# Titan_v1p5.net
KiCad netlist of a schematic drawn in EAGLE
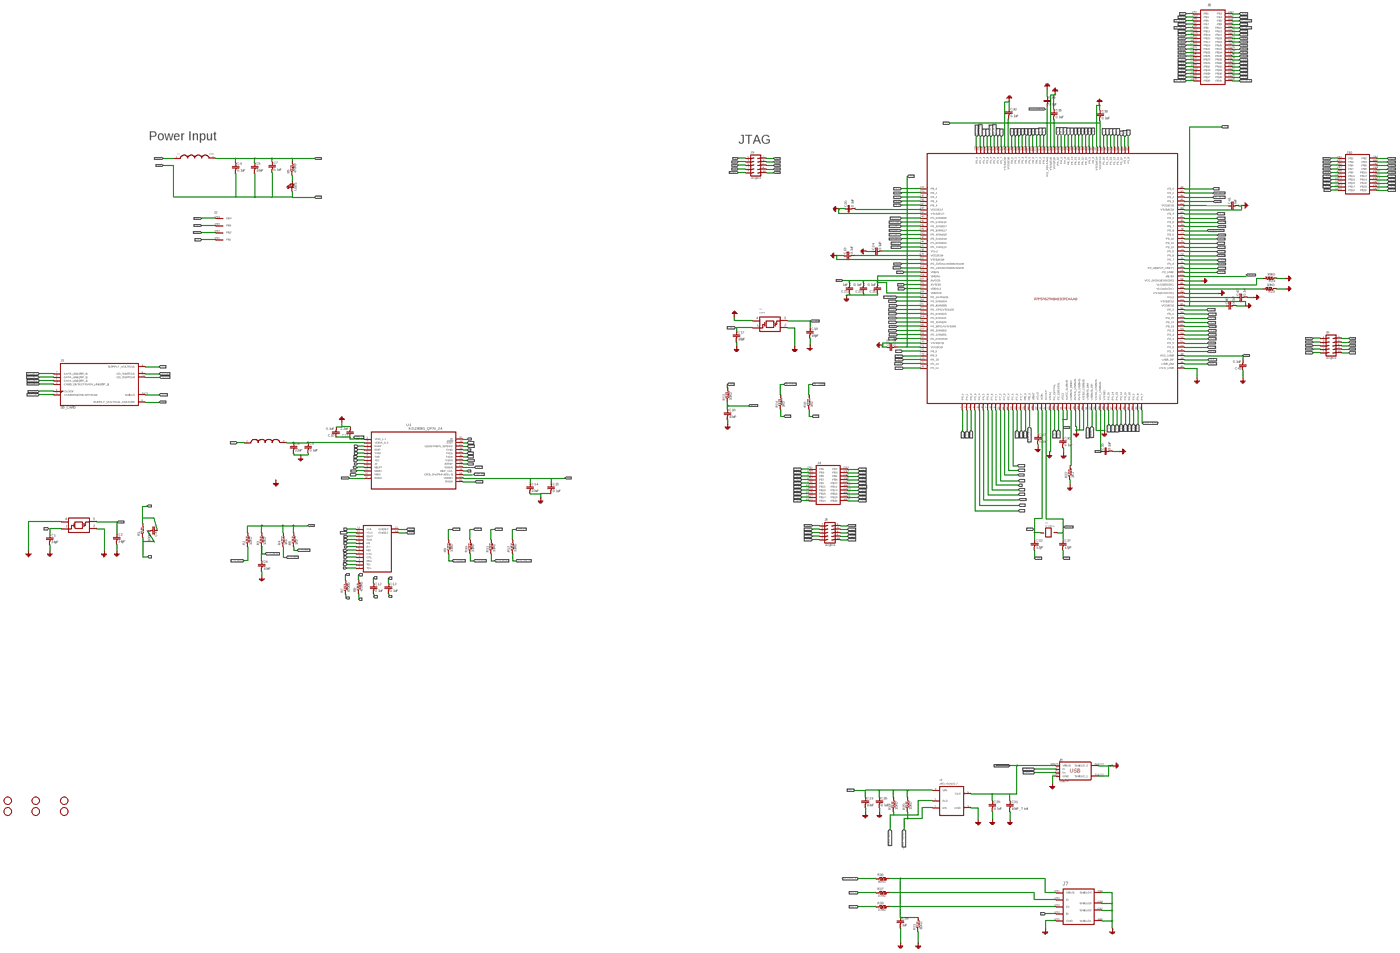
[diagram p0: schematic, sheet 1, overview]
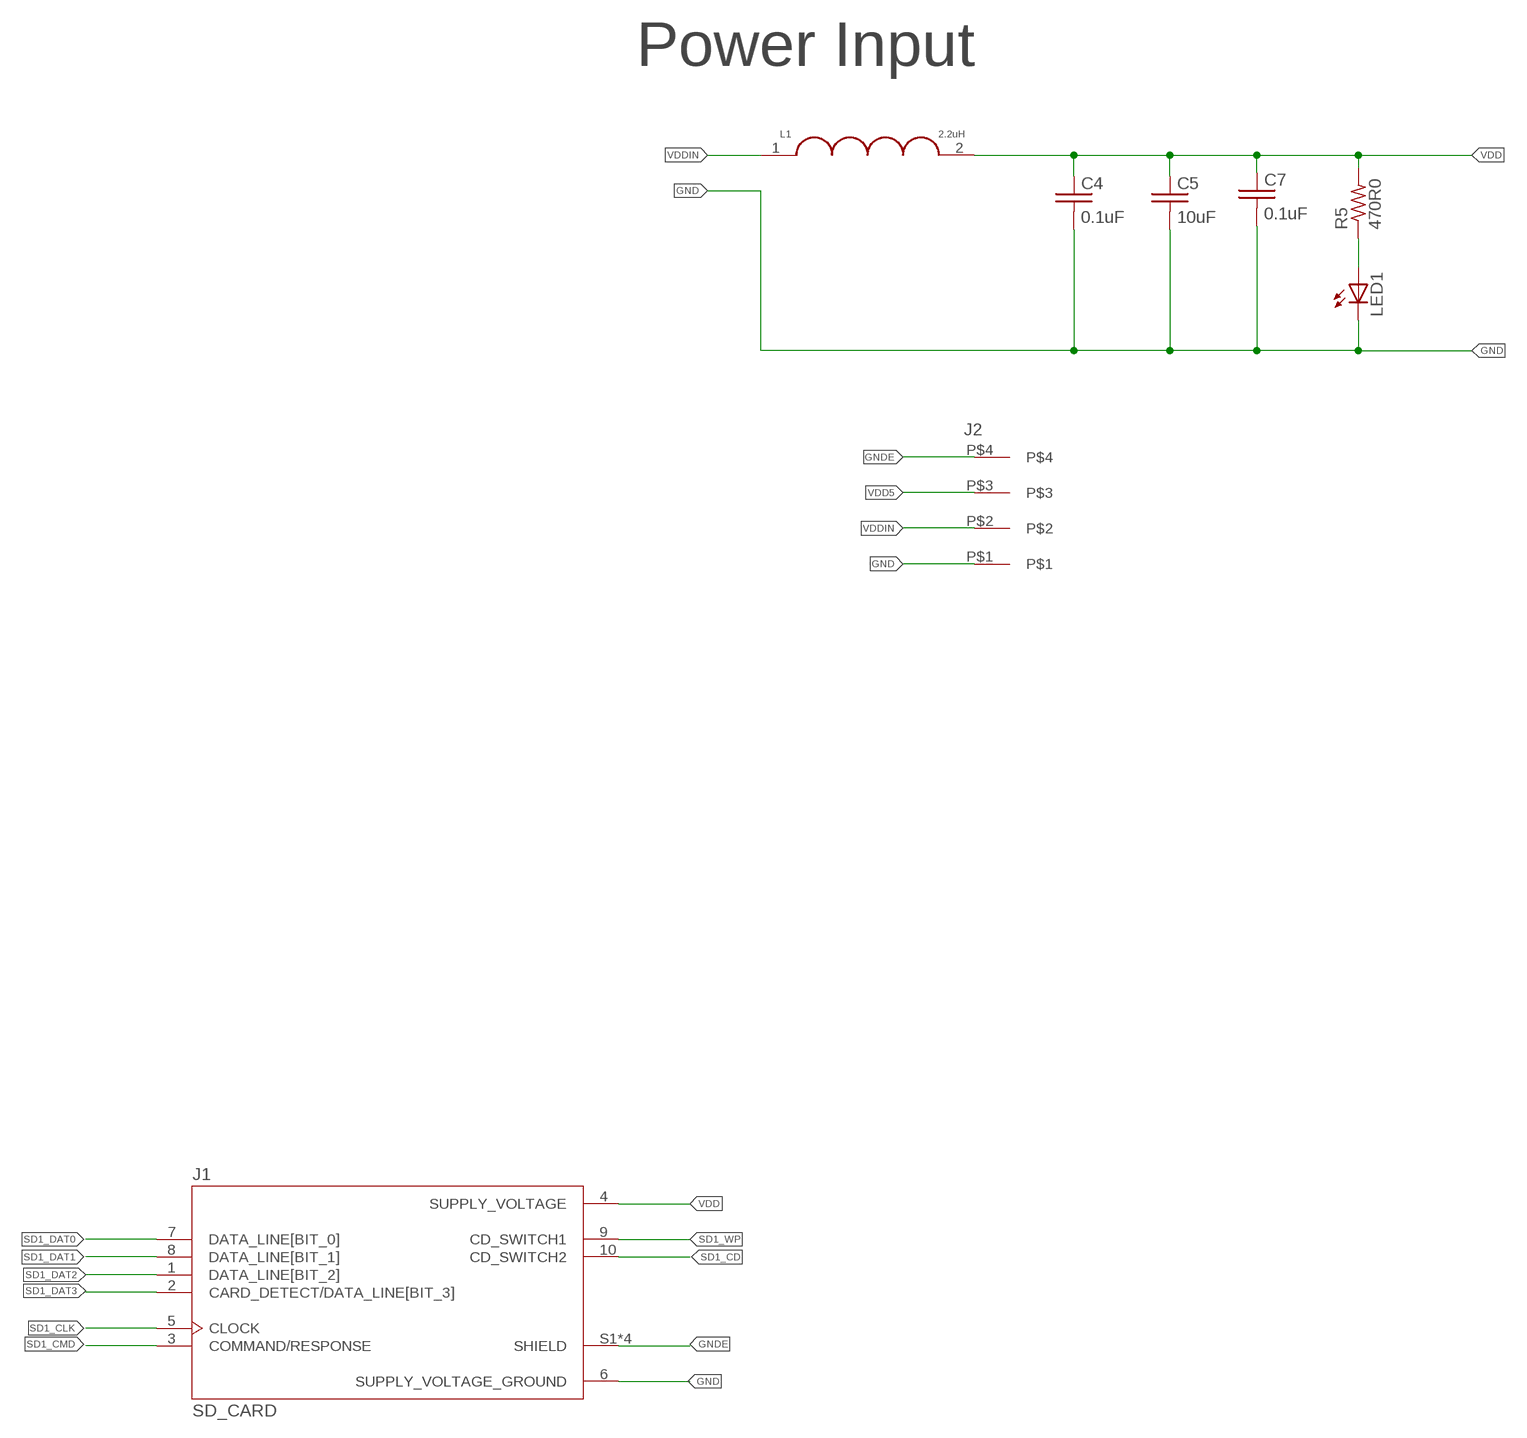
[diagram p1: schematic, sheet 1, part 1 of 5]
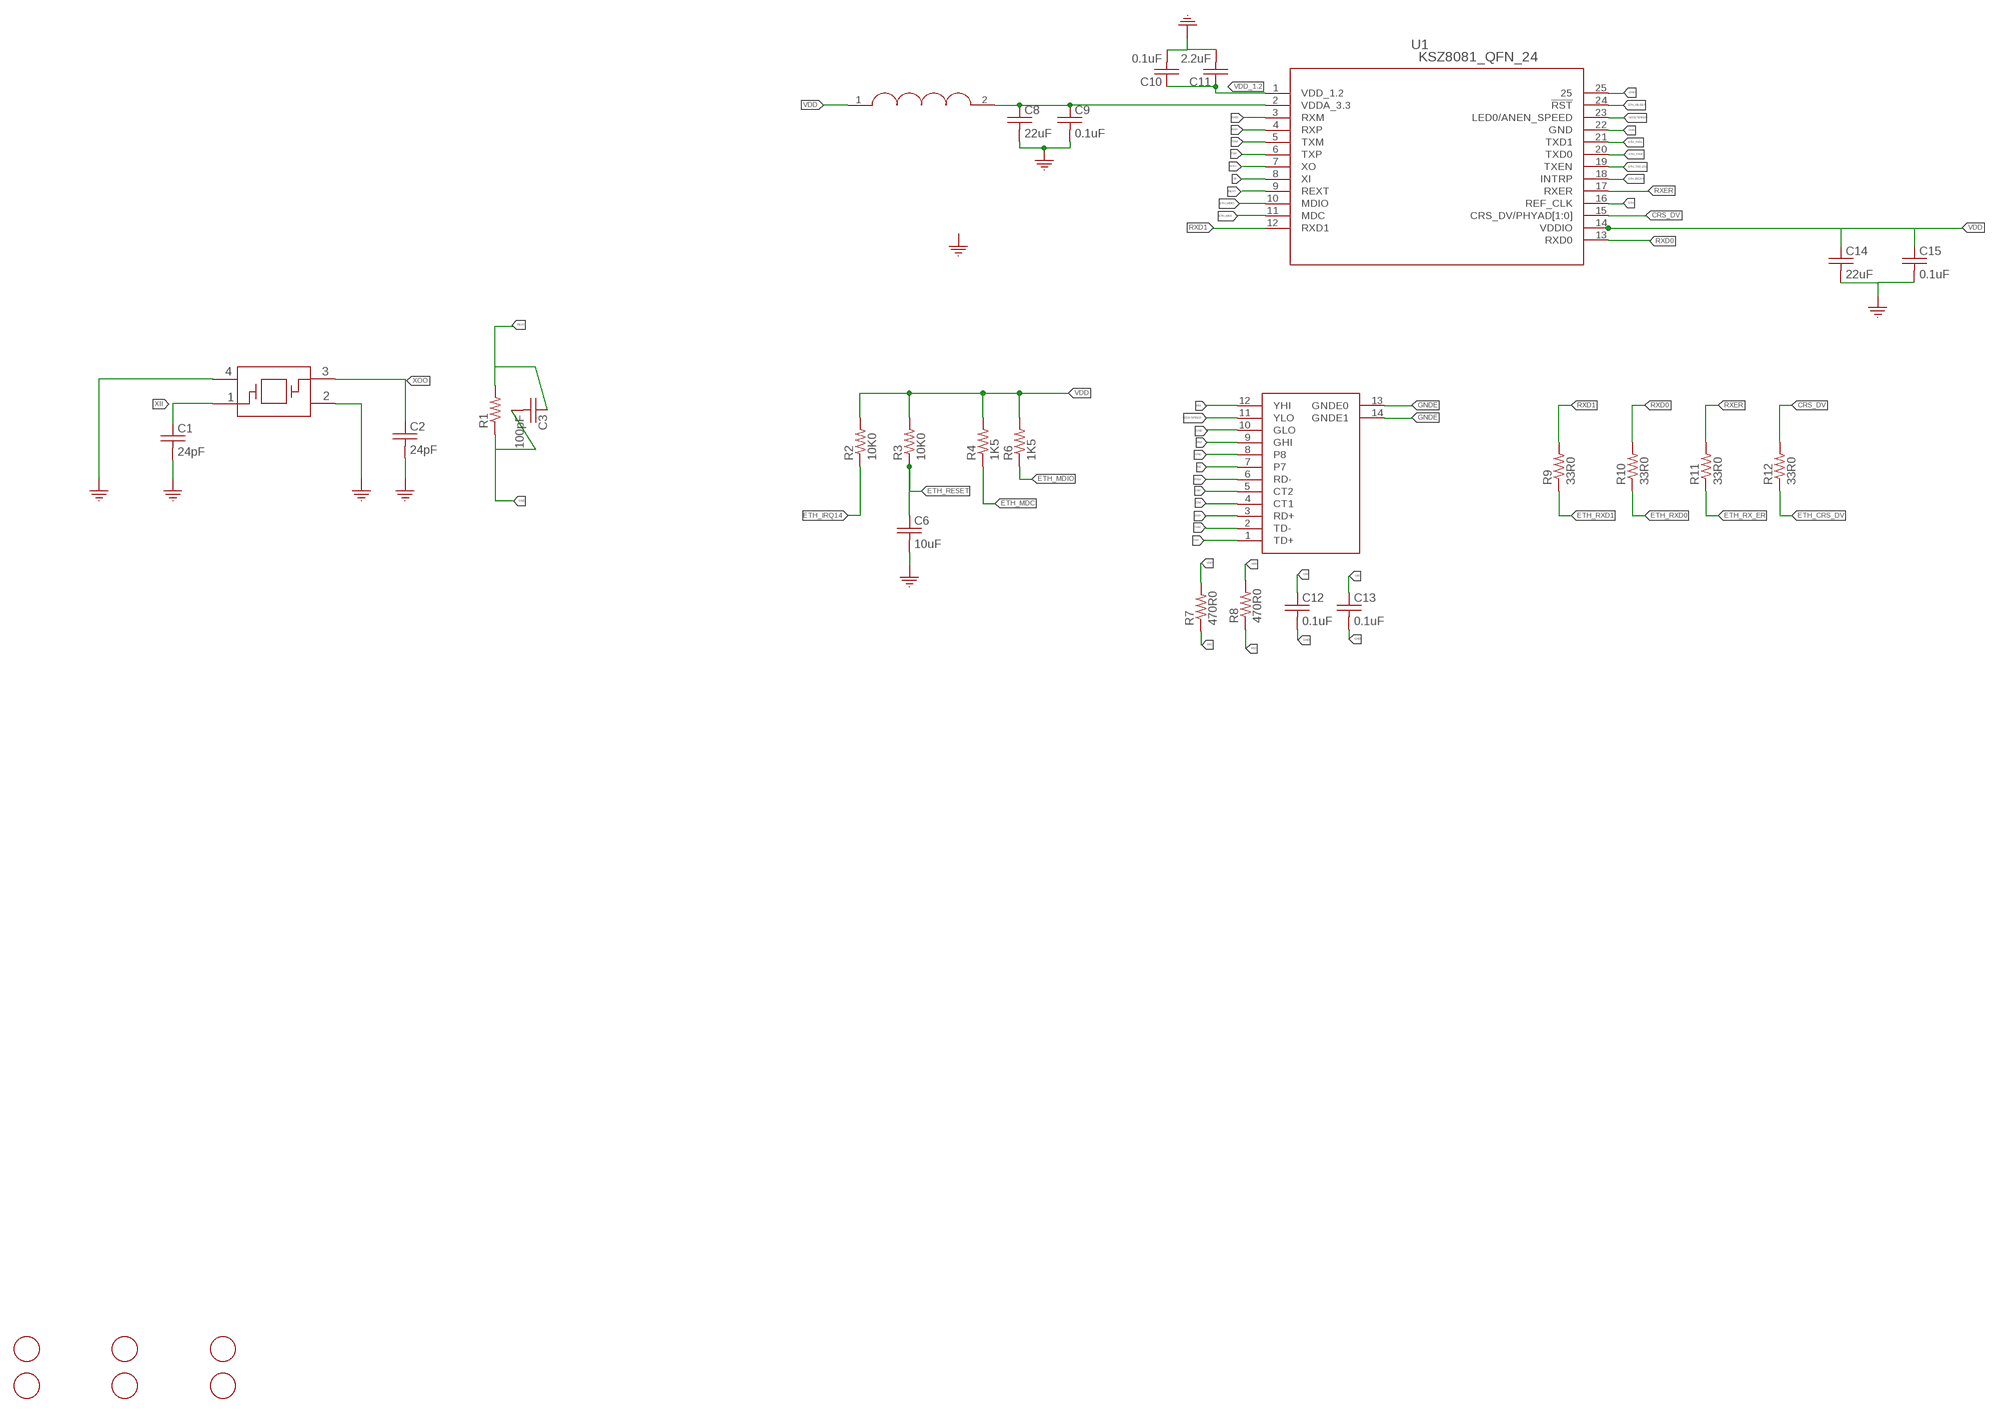
[diagram p2: schematic, sheet 1, part 2 of 5]
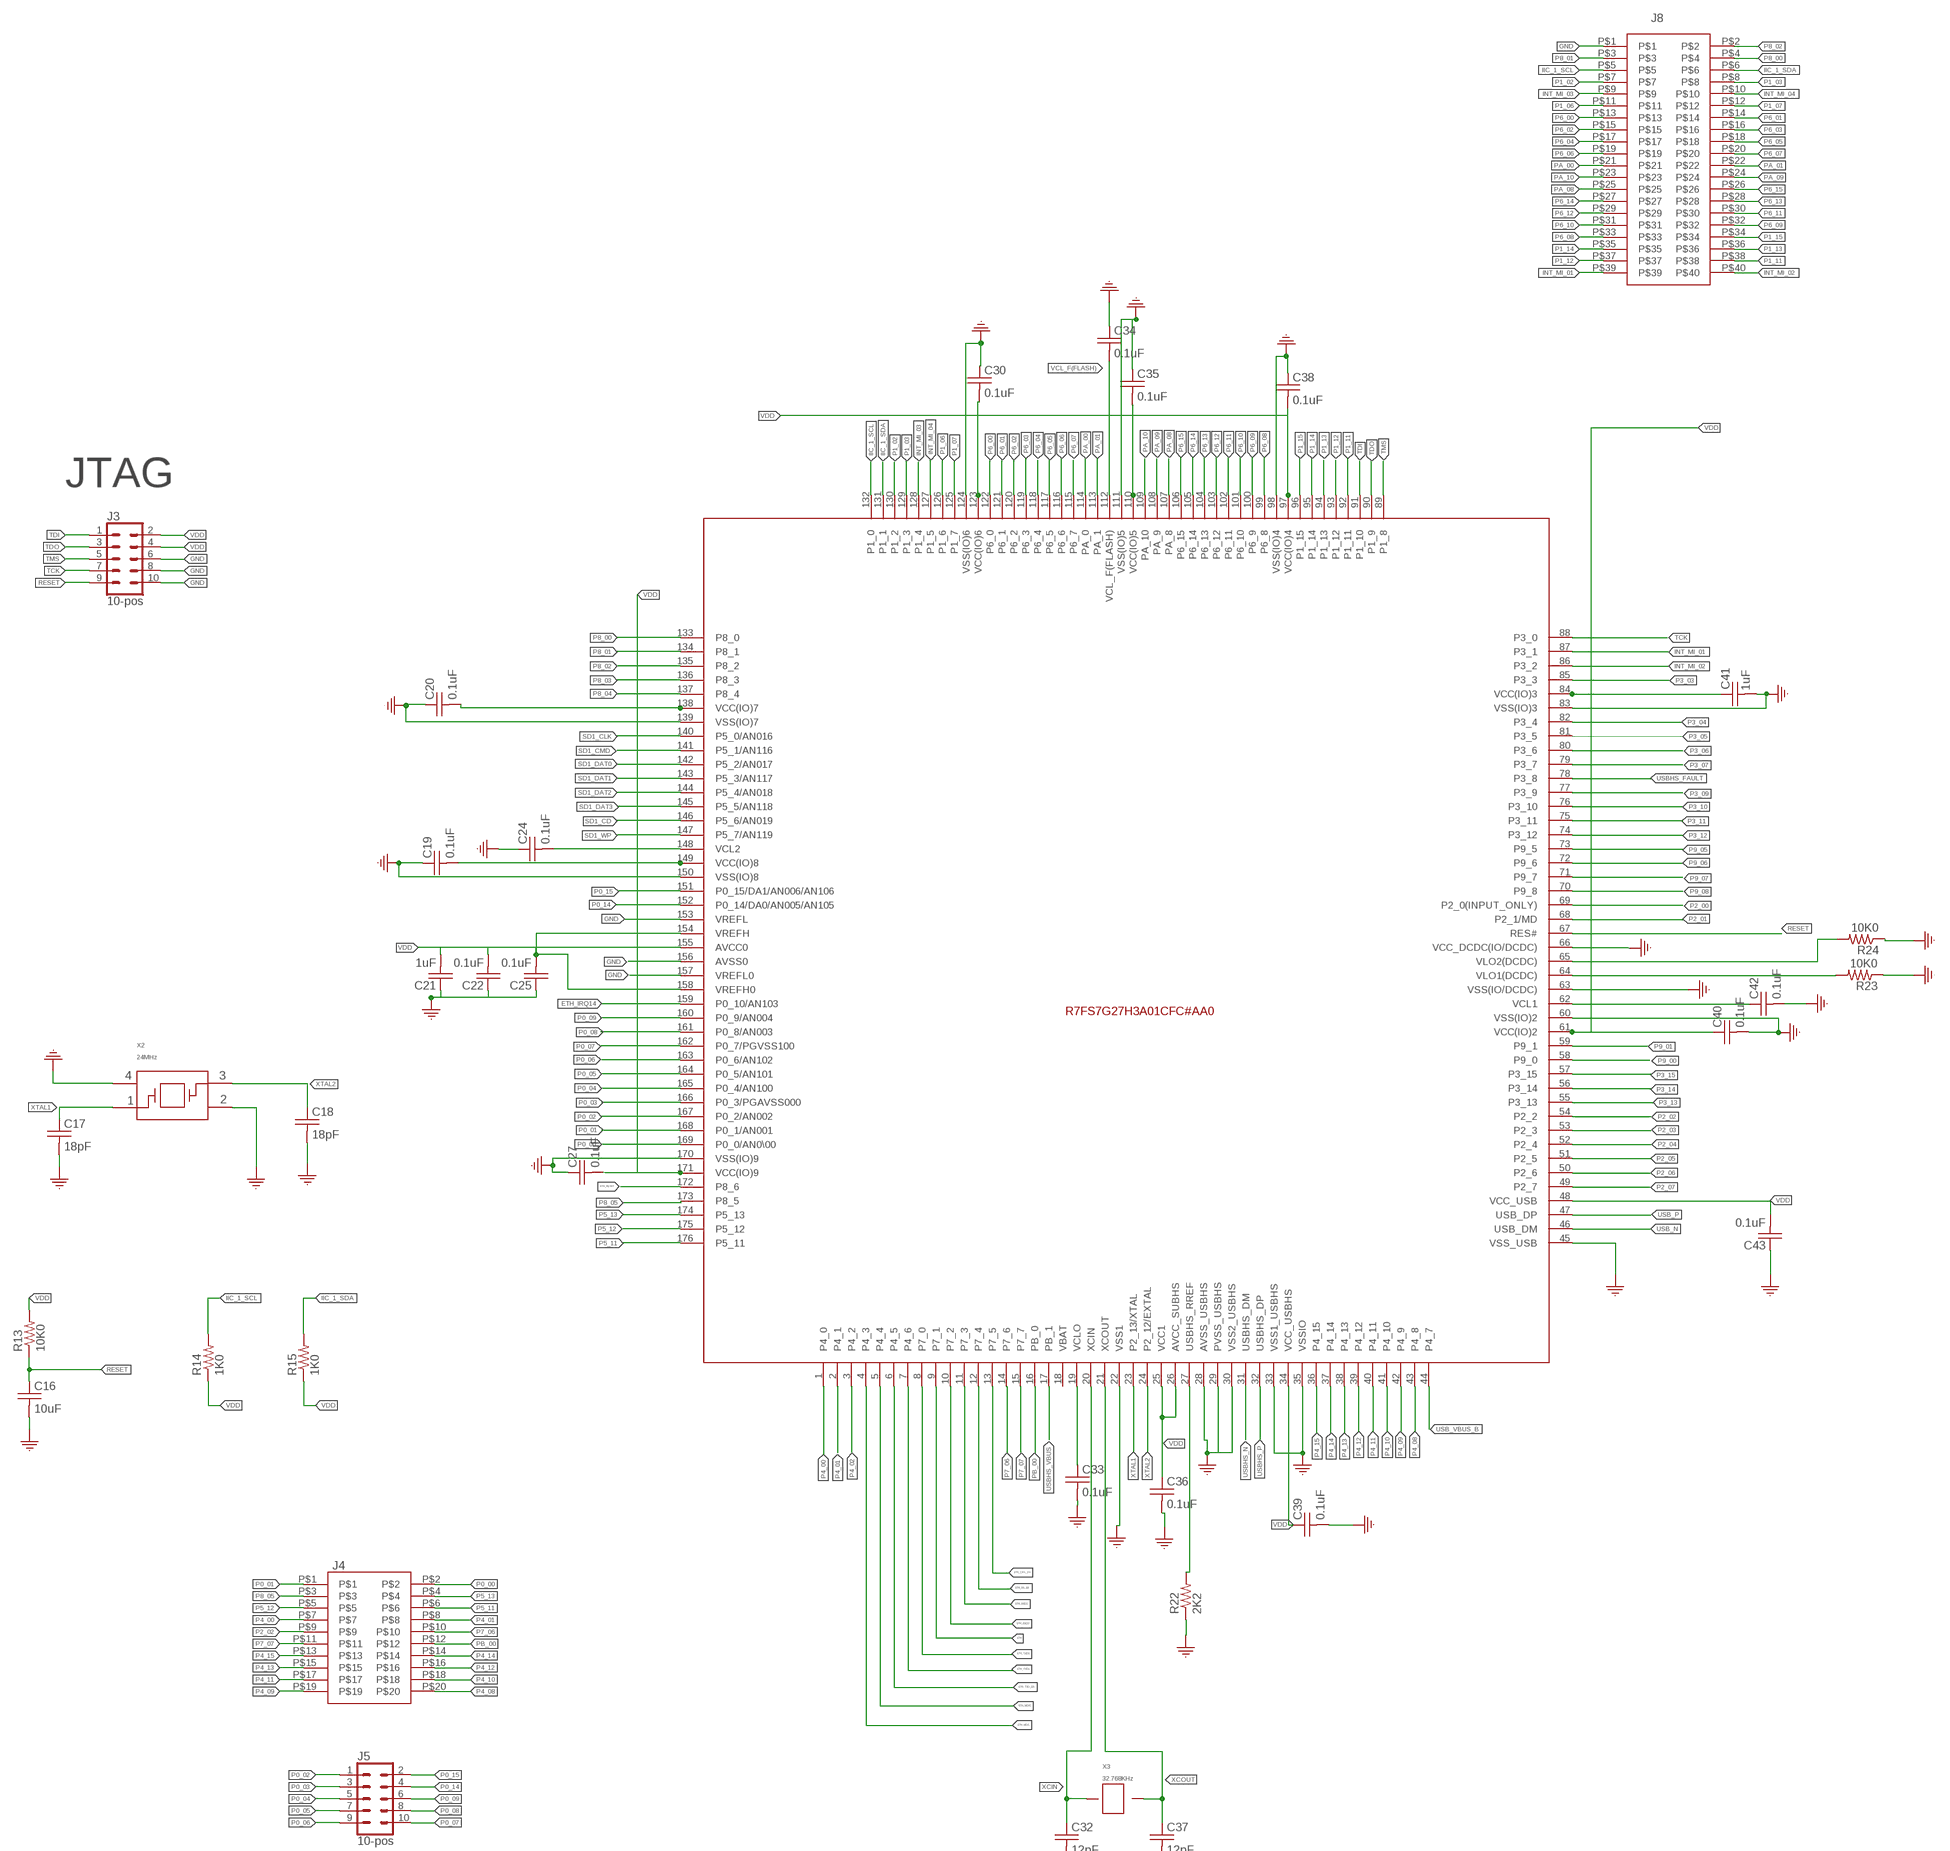
[diagram p3: schematic, sheet 1, part 3 of 5]
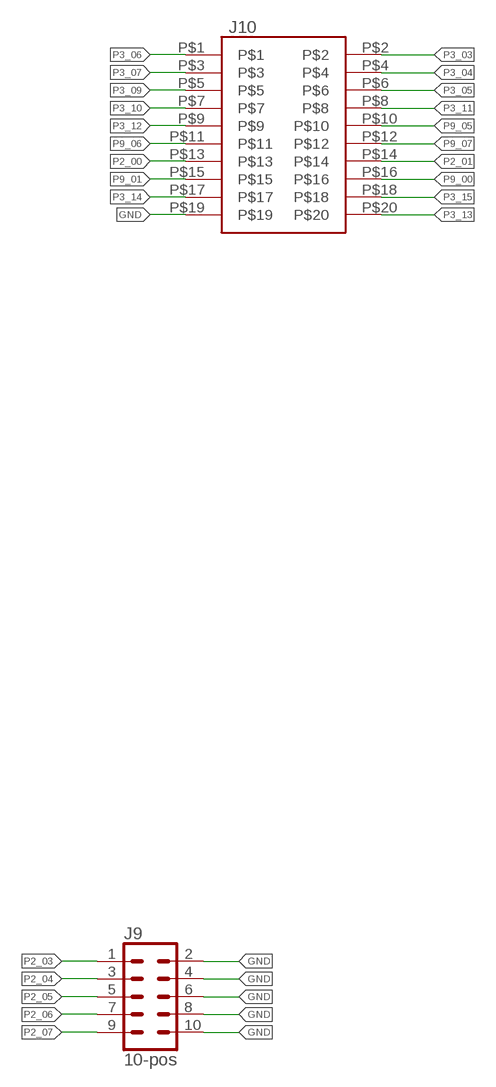
[diagram p4: schematic, sheet 1, part 4 of 5]
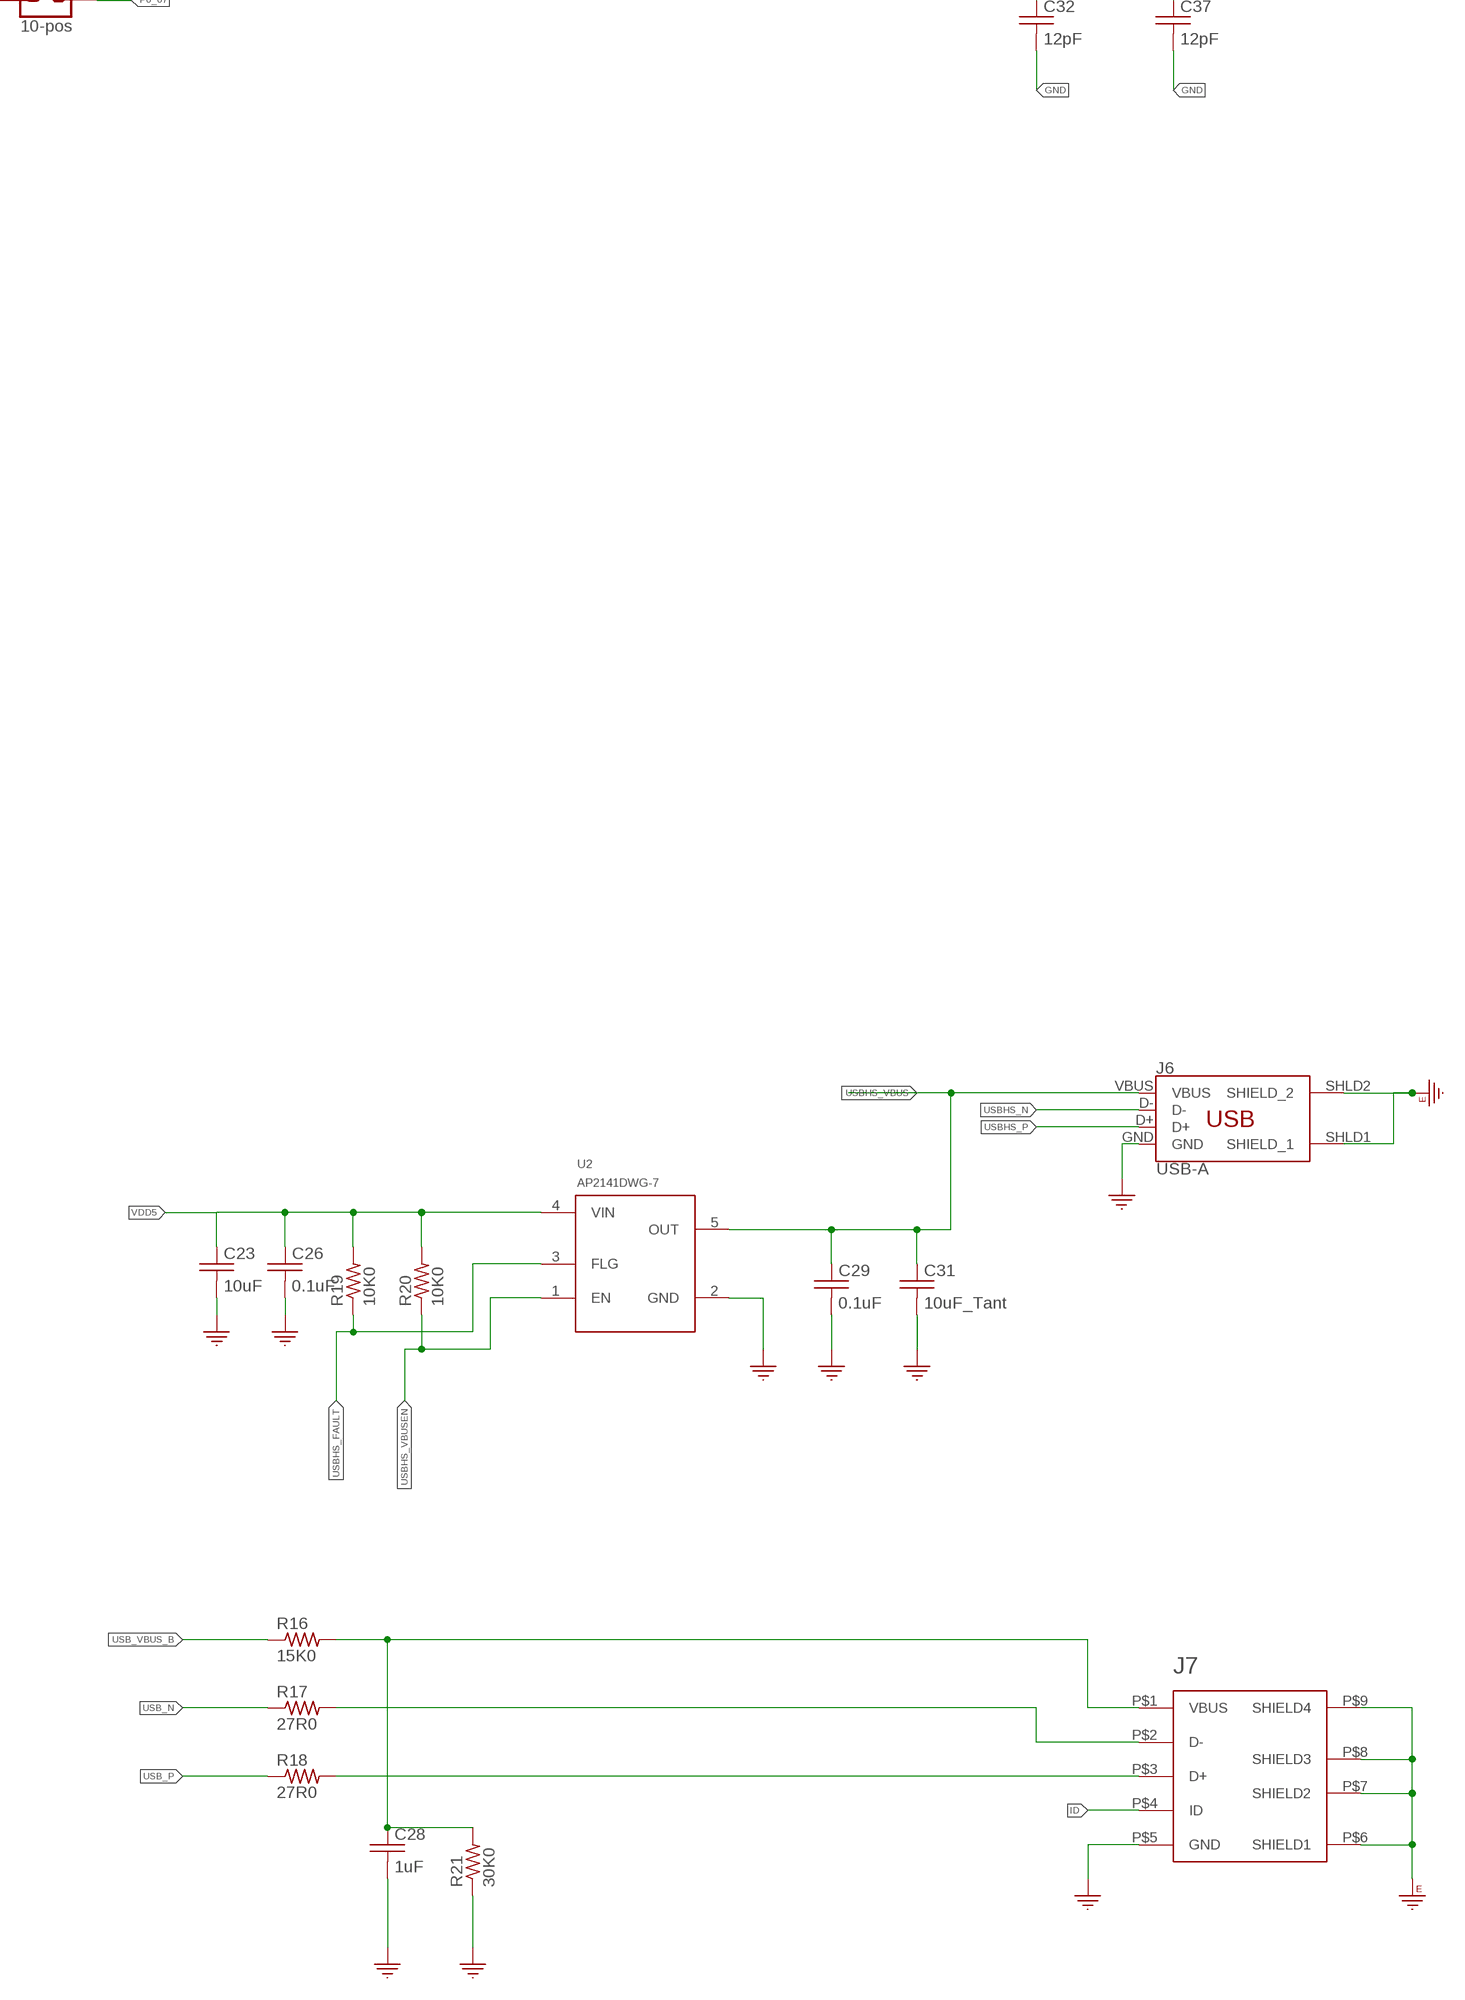
[diagram p5: schematic, sheet 1, part 5 of 5]

(export (version "E")
  (design (tool "Eeschema 10.0.6"))
  (components
    (comp (ref "C1")
      (value "24pF")
      (footprint "eagle-import:0402")
      (fields (field (name "PARTNO") "CC0402GRNPO9BN240"))
      (libsource (lib "eagle-import") (part "C_0402_24PF"))
    )
    (comp (ref "C2")
      (value "24pF")
      (footprint "eagle-import:0402")
      (fields (field (name "PARTNO") "CC0402GRNPO9BN240"))
      (libsource (lib "eagle-import") (part "C_0402_24PF"))
    )
    (comp (ref "C3")
      (value "100pF")
      (footprint "eagle-import:0402")
      (fields (field (name "PARTNO") "CL05C101JB5NNNC"))
      (libsource (lib "eagle-import") (part "C_0402_100PF"))
    )
    (comp (ref "C4")
      (value "0.1uF")
      (footprint "eagle-import:0402")
      (fields (field (name "PARTNO") "CL05F104ZO5NNNC"))
      (libsource (lib "eagle-import") (part "C_0402_0.1UF"))
    )
    (comp (ref "C5")
      (value "10uF")
      (footprint "eagle-import:0402")
      (fields (field (name "PARTNO") "CL05A106MP8NUB8"))
      (libsource (lib "eagle-import") (part "C_0402_10UF"))
    )
    (comp (ref "C6")
      (value "10uF")
      (footprint "eagle-import:0402")
      (fields (field (name "PARTNO") "CL05A106MP8NUB8"))
      (libsource (lib "eagle-import") (part "C_0402_10UF"))
    )
    (comp (ref "C7")
      (value "0.1uF")
      (footprint "eagle-import:0402")
      (fields (field (name "PARTNO") "CL05F104ZO5NNNC"))
      (libsource (lib "eagle-import") (part "C_0402_0.1UF"))
    )
    (comp (ref "C8")
      (value "22uF")
      (footprint "eagle-import:0402")
      (fields (field (name "PARTNO") "CL05A226MQ5N6J8"))
      (libsource (lib "eagle-import") (part "C_0402_22UF"))
    )
    (comp (ref "C9")
      (value "0.1uF")
      (footprint "eagle-import:0402")
      (fields (field (name "PARTNO") "CL05F104ZO5NNNC"))
      (libsource (lib "eagle-import") (part "C_0402_0.1UF"))
    )
    (comp (ref "C10")
      (value "0.1uF")
      (footprint "eagle-import:0402")
      (fields (field (name "PARTNO") "CL05F104ZO5NNNC"))
      (libsource (lib "eagle-import") (part "C_0402_0.1UF"))
    )
    (comp (ref "C11")
      (value "2.2uF")
      (footprint "eagle-import:0402")
      (fields (field (name "PARTNO") "GRM155C81C225ME15D"))
      (libsource (lib "eagle-import") (part "C_0402_2.2UF"))
    )
    (comp (ref "C12")
      (value "0.1uF")
      (footprint "eagle-import:0402")
      (fields (field (name "PARTNO") "CL05F104ZO5NNNC"))
      (libsource (lib "eagle-import") (part "C_0402_0.1UF"))
    )
    (comp (ref "C13")
      (value "0.1uF")
      (footprint "eagle-import:0402")
      (fields (field (name "PARTNO") "CL05F104ZO5NNNC"))
      (libsource (lib "eagle-import") (part "C_0402_0.1UF"))
    )
    (comp (ref "C14")
      (value "22uF")
      (footprint "eagle-import:0402")
      (fields (field (name "PARTNO") "CL05A226MQ5N6J8"))
      (libsource (lib "eagle-import") (part "C_0402_22UF"))
    )
    (comp (ref "C15")
      (value "0.1uF")
      (footprint "eagle-import:0402")
      (fields (field (name "PARTNO") "CL05F104ZO5NNNC"))
      (libsource (lib "eagle-import") (part "C_0402_0.1UF"))
    )
    (comp (ref "C16")
      (value "10uF")
      (footprint "eagle-import:0402")
      (fields (field (name "PARTNO") "CL05A106MP8NUB8"))
      (libsource (lib "eagle-import") (part "C_0402_10UF"))
    )
    (comp (ref "C17")
      (value "18pF")
      (footprint "eagle-import:0402")
      (fields (field (name "PARTNO") "UMK105CG180JV-F"))
      (libsource (lib "eagle-import") (part "C_0402_18PF"))
    )
    (comp (ref "C18")
      (value "18pF")
      (footprint "eagle-import:0402")
      (fields (field (name "PARTNO") "UMK105CG180JV-F"))
      (libsource (lib "eagle-import") (part "C_0402_18PF"))
    )
    (comp (ref "C19")
      (value "0.1uF")
      (footprint "eagle-import:0402")
      (fields (field (name "PARTNO") "CL05F104ZO5NNNC"))
      (libsource (lib "eagle-import") (part "C_0402_0.1UF"))
    )
    (comp (ref "C20")
      (value "0.1uF")
      (footprint "eagle-import:0402")
      (fields (field (name "PARTNO") "CL05F104ZO5NNNC"))
      (libsource (lib "eagle-import") (part "C_0402_0.1UF"))
    )
    (comp (ref "C21")
      (value "1uF")
      (footprint "eagle-import:0402")
      (fields (field (name "PARTNO") "CL05A105KO5NNNC"))
      (libsource (lib "eagle-import") (part "C_0402_1UF"))
    )
    (comp (ref "C22")
      (value "0.1uF")
      (footprint "eagle-import:0402")
      (fields (field (name "PARTNO") "CL05F104ZO5NNNC"))
      (libsource (lib "eagle-import") (part "C_0402_0.1UF"))
    )
    (comp (ref "C23")
      (value "10uF")
      (footprint "eagle-import:0402")
      (fields (field (name "PARTNO") "CL05A106MP8NUB8"))
      (libsource (lib "eagle-import") (part "C_0402_10UF"))
    )
    (comp (ref "C24")
      (value "0.1uF")
      (footprint "eagle-import:0402")
      (fields (field (name "PARTNO") "CL05F104ZO5NNNC"))
      (libsource (lib "eagle-import") (part "C_0402_0.1UF"))
    )
    (comp (ref "C25")
      (value "0.1uF")
      (footprint "eagle-import:0402")
      (fields (field (name "PARTNO") "CL05F104ZO5NNNC"))
      (libsource (lib "eagle-import") (part "C_0402_0.1UF"))
    )
    (comp (ref "C26")
      (value "0.1uF")
      (footprint "eagle-import:0402")
      (fields (field (name "PARTNO") "CL05F104ZO5NNNC"))
      (libsource (lib "eagle-import") (part "C_0402_0.1UF"))
    )
    (comp (ref "C27")
      (value "0.1uF")
      (footprint "eagle-import:0402")
      (fields (field (name "PARTNO") "CL05F104ZO5NNNC"))
      (libsource (lib "eagle-import") (part "C_0402_0.1UF"))
    )
    (comp (ref "C28")
      (value "1uF")
      (footprint "eagle-import:0402")
      (fields (field (name "PARTNO") "CL05A105KO5NNNC"))
      (libsource (lib "eagle-import") (part "C_0402_1UF"))
    )
    (comp (ref "C29")
      (value "0.1uF")
      (footprint "eagle-import:0402")
      (fields (field (name "PARTNO") "CL05F104ZO5NNNC"))
      (libsource (lib "eagle-import") (part "C_0402_0.1UF"))
    )
    (comp (ref "C30")
      (value "0.1uF")
      (footprint "eagle-import:0402")
      (fields (field (name "PARTNO") "CL05F104ZO5NNNC"))
      (libsource (lib "eagle-import") (part "C_0402_0.1UF"))
    )
    (comp (ref "C31")
      (value "10uF_Tant")
      (footprint "eagle-import:C1210")
      (fields (field (name "PARTNO") "TPST106K016H0800"))
      (libsource (lib "eagle-import") (part "C_1210_10UF_TANT"))
    )
    (comp (ref "C32")
      (value "12pF")
      (footprint "eagle-import:0402")
      (fields (field (name "PARTNO") "CL05C120JB5NNNC"))
      (libsource (lib "eagle-import") (part "C_0402_12PF"))
    )
    (comp (ref "C33")
      (value "0.1uF")
      (footprint "eagle-import:0402")
      (fields (field (name "PARTNO") "CL05F104ZO5NNNC"))
      (libsource (lib "eagle-import") (part "C_0402_0.1UF"))
    )
    (comp (ref "C34")
      (value "0.1uF")
      (footprint "eagle-import:0402")
      (fields (field (name "PARTNO") "CL05F104ZO5NNNC"))
      (libsource (lib "eagle-import") (part "C_0402_0.1UF"))
    )
    (comp (ref "C35")
      (value "0.1uF")
      (footprint "eagle-import:0402")
      (fields (field (name "PARTNO") "CL05F104ZO5NNNC"))
      (libsource (lib "eagle-import") (part "C_0402_0.1UF"))
    )
    (comp (ref "C36")
      (value "0.1uF")
      (footprint "eagle-import:0402")
      (fields (field (name "PARTNO") "CL05F104ZO5NNNC"))
      (libsource (lib "eagle-import") (part "C_0402_0.1UF"))
    )
    (comp (ref "C37")
      (value "12pF")
      (footprint "eagle-import:0402")
      (fields (field (name "PARTNO") "CL05C120JB5NNNC"))
      (libsource (lib "eagle-import") (part "C_0402_12PF"))
    )
    (comp (ref "C38")
      (value "0.1uF")
      (footprint "eagle-import:0402")
      (fields (field (name "PARTNO") "CL05F104ZO5NNNC"))
      (libsource (lib "eagle-import") (part "C_0402_0.1UF"))
    )
    (comp (ref "C39")
      (value "0.1uF")
      (footprint "eagle-import:0402")
      (fields (field (name "PARTNO") "CL05F104ZO5NNNC"))
      (libsource (lib "eagle-import") (part "C_0402_0.1UF"))
    )
    (comp (ref "C40")
      (value "0.1uF")
      (footprint "eagle-import:0402")
      (fields (field (name "PARTNO") "CL05F104ZO5NNNC"))
      (libsource (lib "eagle-import") (part "C_0402_0.1UF"))
    )
    (comp (ref "C41")
      (value "1uF")
      (footprint "eagle-import:0402")
      (fields (field (name "PARTNO") "CL05A105KO5NNNC"))
      (libsource (lib "eagle-import") (part "C_0402_1UF"))
    )
    (comp (ref "C42")
      (value "0.1uF")
      (footprint "eagle-import:0402")
      (fields (field (name "PARTNO") "CL05F104ZO5NNNC"))
      (libsource (lib "eagle-import") (part "C_0402_0.1UF"))
    )
    (comp (ref "C43")
      (value "0.1uF")
      (footprint "eagle-import:0402")
      (fields (field (name "PARTNO") "CL05F104ZO5NNNC"))
      (libsource (lib "eagle-import") (part "C_0402_0.1UF"))
    )
    (comp (ref "FB1")
      (value "FB2_603")
      (footprint "eagle-import:0603")
      (fields (field (name "PARTNO") "BLM18PG121SN1D"))
      (libsource (lib "eagle-import") (part "FB_0603_120_OHM0603"))
    )
    (comp (ref "J1")
      (value "SD_CARD")
      (footprint "eagle-import:SD_CARD")
      (fields (field (name "MF") "Amphenol ICC") (field (name "PARTNO") "114-00841-68"))
      (libsource (lib "eagle-import") (part "SD_CARD_1140084168"))
    )
    (comp (ref "J2")
      (value "4-pos")
      (footprint "eagle-import:1X4_3.81MM_PITCH")
      (fields (field (name "PARTNO") "691322310004"))
      (libsource (lib "eagle-import") (part "3.81MM_1_X_4_RT_ANGLE_PLUG_HEADER"))
    )
    (comp (ref "J3")
      (value "10-pos")
      (footprint "eagle-import:2X5")
      (fields (field (name "PARTNO") "PH2RA-10-UA"))
      (libsource (lib "eagle-import") (part "CONN_05X2_RAPTH"))
    )
    (comp (ref "J4")
      (value "20-pos")
      (footprint "eagle-import:2_X_10_.1_INCH")
      (fields (field (name "PARTNO") "67996-420HLF"))
      (libsource (lib "eagle-import") (part "2_X_10_HEADER_GENERIC"))
    )
    (comp (ref "J5")
      (value "10-pos")
      (footprint "eagle-import:2X5")
      (fields (field (name "PARTNO") "PH2RA-10-UA"))
      (libsource (lib "eagle-import") (part "CONN_05X2_RAPTH"))
    )
    (comp (ref "J6")
      (value "USB-A")
      (footprint "eagle-import:USB_A_SMT")
      (fields (field (name "PARTNO") "87583-3010RPALF"))
      (libsource (lib "eagle-import") (part "USB_A"))
    )
    (comp (ref "J7")
      (value "USB-B-Micro")
      (footprint "eagle-import:USB_MICRO-B")
      (fields (field (name "PARTNO") "10118192-0002LF"))
      (libsource (lib "eagle-import") (part "USB_MICRO-B"))
    )
    (comp (ref "J8")
      (value "40-pos")
      (footprint "eagle-import:HEADER_2_X_20_.1_INCH")
      (fields (field (name "PARTNO") "61304021021"))
      (libsource (lib "eagle-import") (part "HEADER_2_X_20_GENERIC"))
    )
    (comp (ref "J9")
      (value "10-pos")
      (footprint "eagle-import:2X5")
      (fields (field (name "PARTNO") "PH2RA-10-UA"))
      (libsource (lib "eagle-import") (part "CONN_05X2_RAPTH"))
    )
    (comp (ref "J10")
      (value "20-pos")
      (footprint "eagle-import:2_X_10_.1_INCH")
      (fields (field (name "PARTNO") "67996-420HLF"))
      (libsource (lib "eagle-import") (part "2_X_10_HEADER_GENERIC"))
    )
    (comp (ref "L1")
      (value "2.2uH")
      (footprint "eagle-import:1008")
      (fields (field (name "PARTNO") "LQM2HPN2R2MG0L"))
      (libsource (lib "eagle-import") (part "INDUCTOR_1008_2.2_MH_1.3A"))
    )
    (comp (ref "LED1")
      (value "Green")
      (footprint "eagle-import:0805")
      (fields (field (name "PARTNO") "LG R971-KN-1"))
      (libsource (lib "eagle-import") (part "LED_0805_GREEN"))
    )
    (comp (ref "R1")
      (value "6K49")
      (footprint "eagle-import:0402")
      (fields (field (name "PARTNO") "RMCF0402FT6K49"))
      (libsource (lib "eagle-import") (part "R_0402_6K49"))
    )
    (comp (ref "R2")
      (value "10K0")
      (footprint "eagle-import:0402")
      (fields (field (name "PARTNO") "RMCF0402JT10K0"))
      (libsource (lib "eagle-import") (part "R_0402_10K0"))
    )
    (comp (ref "R3")
      (value "10K0")
      (footprint "eagle-import:0402")
      (fields (field (name "PARTNO") "RMCF0402JT10K0"))
      (libsource (lib "eagle-import") (part "R_0402_10K0"))
    )
    (comp (ref "R4")
      (value "1K5")
      (footprint "eagle-import:0402")
      (fields (field (name "PARTNO") "RMCF0402JT1K50"))
      (libsource (lib "eagle-import") (part "R_0402_1K5"))
    )
    (comp (ref "R5")
      (value "470R0")
      (footprint "eagle-import:0402")
      (fields (field (name "PARTNO") "RMCF0402JT470R"))
      (libsource (lib "eagle-import") (part "R_0402_470R0"))
    )
    (comp (ref "R6")
      (value "1K5")
      (footprint "eagle-import:0402")
      (fields (field (name "PARTNO") "RMCF0402JT1K50"))
      (libsource (lib "eagle-import") (part "R_0402_1K5"))
    )
    (comp (ref "R7")
      (value "470R0")
      (footprint "eagle-import:0402")
      (fields (field (name "PARTNO") "RMCF0402JT470R"))
      (libsource (lib "eagle-import") (part "R_0402_470R0"))
    )
    (comp (ref "R8")
      (value "470R0")
      (footprint "eagle-import:0402")
      (fields (field (name "PARTNO") "RMCF0402JT470R"))
      (libsource (lib "eagle-import") (part "R_0402_470R0"))
    )
    (comp (ref "R9")
      (value "33R0")
      (footprint "eagle-import:0402")
      (fields (field (name "PARTNO") "RMCF0402JT33R0"))
      (libsource (lib "eagle-import") (part "R_0402_33R0"))
    )
    (comp (ref "R10")
      (value "33R0")
      (footprint "eagle-import:0402")
      (fields (field (name "PARTNO") "RMCF0402JT33R0"))
      (libsource (lib "eagle-import") (part "R_0402_33R0"))
    )
    (comp (ref "R11")
      (value "33R0")
      (footprint "eagle-import:0402")
      (fields (field (name "PARTNO") "RMCF0402JT33R0"))
      (libsource (lib "eagle-import") (part "R_0402_33R0"))
    )
    (comp (ref "R12")
      (value "33R0")
      (footprint "eagle-import:0402")
      (fields (field (name "PARTNO") "RMCF0402JT33R0"))
      (libsource (lib "eagle-import") (part "R_0402_33R0"))
    )
    (comp (ref "R13")
      (value "10K0")
      (footprint "eagle-import:0402")
      (fields (field (name "PARTNO") "RMCF0402JT10K0"))
      (libsource (lib "eagle-import") (part "R_0402_10K0"))
    )
    (comp (ref "R14")
      (value "1K0")
      (footprint "eagle-import:0402")
      (fields (field (name "PARTNO") "CRG0402J1K0"))
      (libsource (lib "eagle-import") (part "R_0402_1K0"))
    )
    (comp (ref "R15")
      (value "1K0")
      (footprint "eagle-import:0402")
      (fields (field (name "PARTNO") "CRG0402J1K0"))
      (libsource (lib "eagle-import") (part "R_0402_1K0"))
    )
    (comp (ref "R16")
      (value "15K0")
      (footprint "eagle-import:0402")
      (fields (field (name "PARTNO") "RMCF0402JT15K0"))
      (libsource (lib "eagle-import") (part "R_0402_15K0"))
    )
    (comp (ref "R17")
      (value "27R0")
      (footprint "eagle-import:0402")
      (fields (field (name "PARTNO") "RMCF0402JT27R0"))
      (libsource (lib "eagle-import") (part "R_0402_27R0"))
    )
    (comp (ref "R18")
      (value "27R0")
      (footprint "eagle-import:0402")
      (fields (field (name "PARTNO") "RMCF0402JT27R0"))
      (libsource (lib "eagle-import") (part "R_0402_27R0"))
    )
    (comp (ref "R19")
      (value "10K0")
      (footprint "eagle-import:0402")
      (fields (field (name "PARTNO") "RMCF0402JT10K0"))
      (libsource (lib "eagle-import") (part "R_0402_10K0"))
    )
    (comp (ref "R20")
      (value "10K0")
      (footprint "eagle-import:0402")
      (fields (field (name "PARTNO") "RMCF0402JT10K0"))
      (libsource (lib "eagle-import") (part "R_0402_10K0"))
    )
    (comp (ref "R21")
      (value "30K0")
      (footprint "eagle-import:0402")
      (fields (field (name "PARTNO") "RC0402JR-0730KL"))
      (libsource (lib "eagle-import") (part "R_0402_30K0"))
    )
    (comp (ref "R22")
      (value "2K2")
      (footprint "eagle-import:0402")
      (fields (field (name "PARTNO") "RMCF0402JT2K20"))
      (libsource (lib "eagle-import") (part "R_0402_2K2"))
    )
    (comp (ref "R23")
      (value "10K0")
      (footprint "eagle-import:0402")
      (fields (field (name "PARTNO") "RMCF0402JT10K0"))
      (libsource (lib "eagle-import") (part "R_0402_10K0"))
    )
    (comp (ref "R24")
      (value "10K0")
      (footprint "eagle-import:0402")
      (fields (field (name "PARTNO") "RMCF0402JT10K0"))
      (libsource (lib "eagle-import") (part "R_0402_10K0"))
    )
    (comp (ref "RJ1")
      (value "RJ45")
      (footprint "eagle-import:RJ45_TH_ELEC")
      (fields (field (name "PARTNO") "13F-64GYD2PL2NL"))
      (libsource (lib "eagle-import") (part "RJ45_WITH_ELEC"))
    )
    (comp (ref "U$1")
      (value "FIDUCIAL_1MM")
      (footprint "eagle-import:FIDUCIAL_1MM")
      (libsource (lib "eagle-import") (part "FIDUCIAL_1MM"))
    )
    (comp (ref "U$2")
      (value "FIDUCIAL_1MM")
      (footprint "eagle-import:FIDUCIAL_1MM")
      (libsource (lib "eagle-import") (part "FIDUCIAL_1MM"))
    )
    (comp (ref "U$3")
      (value "FIDUCIAL_1MM")
      (footprint "eagle-import:FIDUCIAL_1MM")
      (libsource (lib "eagle-import") (part "FIDUCIAL_1MM"))
    )
    (comp (ref "U$4")
      (value "FIDUCIAL_1MM")
      (footprint "eagle-import:FIDUCIAL_1MM")
      (libsource (lib "eagle-import") (part "FIDUCIAL_1MM"))
    )
    (comp (ref "U$5")
      (value "FIDUCIAL_1MM")
      (footprint "eagle-import:FIDUCIAL_1MM")
      (libsource (lib "eagle-import") (part "FIDUCIAL_1MM"))
    )
    (comp (ref "U$6")
      (value "FIDUCIAL_1MM")
      (footprint "eagle-import:FIDUCIAL_1MM")
      (libsource (lib "eagle-import") (part "FIDUCIAL_1MM"))
    )
    (comp (ref "U1")
      (value "KSZ8081_QFN_24")
      (footprint "eagle-import:QFN-24-M")
      (fields (field (name "PARTNO") "KSZ8081RNACA"))
      (libsource (lib "eagle-import") (part "KSZ8081RNACAQFN-24-M"))
    )
    (comp (ref "U2")
      (value "AP2151DWG-7")
      (footprint "eagle-import:SOT-23-5")
      (fields (field (name "PARTNO") "AP2151WG-7"))
      (libsource (lib "eagle-import") (part "AP2151DWG-7"))
    )
    (comp (ref "U3")
      (value "S7G2LQFP176")
      (footprint "eagle-import:LQFP176_24X24")
      (fields (field (name "PARTNO") "R7FS7G27H3A01CFC#AA0"))
      (libsource (lib "eagle-import") (part "RENESAS_S7G2_X_176"))
    )
    (comp (ref "X1")
      (value "25MHz")
      (footprint "eagle-import:SMD_3225")
      (fields (field (name "PARTNO") "FA-238 25.0000MB-B3"))
      (libsource (lib "eagle-import") (part "XTAL_25_MHZ"))
    )
    (comp (ref "X2")
      (value "24MHz")
      (footprint "eagle-import:SMD_3225")
      (fields (field (name "PARTNO") "FA-238 24.0000MB-C3 "))
      (libsource (lib "eagle-import") (part "XTAL_24_MHZ"))
    )
    (comp (ref "X3")
      (value "32.768KHz")
      (footprint "eagle-import:SMD_X_2_PADS")
      (fields (field (name "PARTNO") "ABS07-32.768KHZ-T"))
      (libsource (lib "eagle-import") (part "XTAL_32.768KHZ"))
    )
  )
  (nets
    (net (code "1") (name "C58") (class "Default")
      (node (ref "C12") (pin "P$1") (pinfunction "1_P$1") (pintype "passive"))
      (node (ref "RJ1") (pin "4") (pinfunction "CT1_4") (pintype "bidirectional"))
    )
    (net (code "2") (name "C60") (class "Default")
      (node (ref "C13") (pin "P$1") (pinfunction "1_P$1") (pintype "passive"))
      (node (ref "RJ1") (pin "5") (pinfunction "CT2_5") (pintype "bidirectional"))
    )
    (net (code "3") (name "CRS_DV") (class "Default")
      (node (ref "R12") (pin "P$2") (pinfunction "2_P$2") (pintype "passive"))
      (node (ref "U1") (pin "15") (pinfunction "CRS_DV/PHYAD[1:0]_15") (pintype "bidirectional"))
    )
    (net (code "4") (name "ETH") (class "Default")
      (node (ref "U1") (pin "16") (pinfunction "REF_CLK_16") (pintype "bidirectional"))
      (node (ref "U3") (pin "9") (pinfunction "P7_1_9") (pintype "bidirectional"))
    )
    (net (code "5") (name "ETH_CRS_DV") (class "Default")
      (node (ref "R12") (pin "P$1") (pinfunction "1_P$1") (pintype "passive"))
      (node (ref "U3") (pin "13") (pinfunction "P7_5_13") (pintype "bidirectional"))
    )
    (net (code "6") (name "ETH_IRQ14") (class "Default")
      (node (ref "R2") (pin "P$1") (pinfunction "1_P$1") (pintype "passive"))
      (node (ref "U1") (pin "18") (pinfunction "INTRP_18") (pintype "bidirectional"))
      (node (ref "U3") (pin "159") (pinfunction "P0_10/AN103_159") (pintype "bidirectional"))
    )
    (net (code "7") (name "ETH_MDC") (class "Default")
      (node (ref "R4") (pin "P$1") (pinfunction "1_P$1") (pintype "passive"))
      (node (ref "U1") (pin "11") (pinfunction "MDC_11") (pintype "input"))
      (node (ref "U3") (pin "4") (pinfunction "P4_3_4") (pintype "bidirectional"))
    )
    (net (code "8") (name "ETH_MDIO") (class "Default")
      (node (ref "R6") (pin "P$1") (pinfunction "1_P$1") (pintype "passive"))
      (node (ref "U1") (pin "10") (pinfunction "MDIO_10") (pintype "bidirectional"))
      (node (ref "U3") (pin "5") (pinfunction "P4_4_5") (pintype "bidirectional"))
    )
    (net (code "9") (name "ETH_RESET") (class "Default")
      (node (ref "C6") (pin "P$1") (pinfunction "1_P$1") (pintype "passive"))
      (node (ref "R3") (pin "P$1") (pinfunction "1_P$1") (pintype "passive"))
      (node (ref "U1") (pin "24") (pinfunction "~{RST}_24") (pintype "input"))
      (node (ref "U3") (pin "172") (pinfunction "P8_6_172") (pintype "bidirectional"))
    )
    (net (code "10") (name "ETH_RXD0") (class "Default")
      (node (ref "R10") (pin "P$1") (pinfunction "1_P$1") (pintype "passive"))
      (node (ref "U3") (pin "10") (pinfunction "P7_2_10") (pintype "bidirectional"))
    )
    (net (code "11") (name "ETH_RXD1") (class "Default")
      (node (ref "R9") (pin "P$1") (pinfunction "1_P$1") (pintype "passive"))
      (node (ref "U3") (pin "11") (pinfunction "P7_3_11") (pintype "bidirectional"))
    )
    (net (code "12") (name "ETH_RX_ER") (class "Default")
      (node (ref "R11") (pin "P$1") (pinfunction "1_P$1") (pintype "passive"))
      (node (ref "U3") (pin "12") (pinfunction "P7_4_12") (pintype "bidirectional"))
    )
    (net (code "13") (name "ETH_TXD0") (class "Default")
      (node (ref "U1") (pin "20") (pinfunction "TXD0_20") (pintype "input"))
      (node (ref "U3") (pin "8") (pinfunction "P7_0_8") (pintype "bidirectional"))
    )
    (net (code "14") (name "ETH_TXD1") (class "Default")
      (node (ref "U1") (pin "21") (pinfunction "TXD1_21") (pintype "bidirectional"))
      (node (ref "U3") (pin "7") (pinfunction "P4_6_7") (pintype "bidirectional"))
    )
    (net (code "15") (name "ETH_TXD_EN") (class "Default")
      (node (ref "U1") (pin "19") (pinfunction "TXEN_19") (pintype "input"))
      (node (ref "U3") (pin "6") (pinfunction "P4_5_6") (pintype "bidirectional"))
    )
    (net (code "16") (name "GND") (class "Default")
      (node (ref "C1") (pin "P$2") (pinfunction "2_P$2") (pintype "passive"))
      (node (ref "C10") (pin "P$2") (pinfunction "2_P$2") (pintype "passive"))
      (node (ref "C11") (pin "P$2") (pinfunction "2_P$2") (pintype "passive"))
      (node (ref "C12") (pin "P$2") (pinfunction "2_P$2") (pintype "passive"))
      (node (ref "C13") (pin "P$2") (pinfunction "2_P$2") (pintype "passive"))
      (node (ref "C14") (pin "P$2") (pinfunction "2_P$2") (pintype "passive"))
      (node (ref "C15") (pin "P$2") (pinfunction "2_P$2") (pintype "passive"))
      (node (ref "C16") (pin "P$2") (pinfunction "2_P$2") (pintype "passive"))
      (node (ref "C17") (pin "P$2") (pinfunction "2_P$2") (pintype "passive"))
      (node (ref "C18") (pin "P$2") (pinfunction "2_P$2") (pintype "passive"))
      (node (ref "C19") (pin "P$1") (pinfunction "1_P$1") (pintype "passive"))
      (node (ref "C2") (pin "P$2") (pinfunction "2_P$2") (pintype "passive"))
      (node (ref "C20") (pin "P$1") (pinfunction "1_P$1") (pintype "passive"))
      (node (ref "C21") (pin "P$1") (pinfunction "1_P$1") (pintype "passive"))
      (node (ref "C22") (pin "P$1") (pinfunction "1_P$1") (pintype "passive"))
      (node (ref "C23") (pin "P$2") (pinfunction "2_P$2") (pintype "passive"))
      (node (ref "C24") (pin "P$1") (pinfunction "1_P$1") (pintype "passive"))
      (node (ref "C25") (pin "P$1") (pinfunction "1_P$1") (pintype "passive"))
      (node (ref "C26") (pin "P$2") (pinfunction "2_P$2") (pintype "passive"))
      (node (ref "C27") (pin "P$1") (pinfunction "1_P$1") (pintype "passive"))
      (node (ref "C28") (pin "P$2") (pinfunction "2_P$2") (pintype "passive"))
      (node (ref "C29") (pin "P$2") (pinfunction "2_P$2") (pintype "passive"))
      (node (ref "C3") (pin "P$2") (pinfunction "2_P$2") (pintype "passive"))
      (node (ref "C30") (pin "P$1") (pinfunction "1_P$1") (pintype "passive"))
      (node (ref "C31") (pin "2") (pinfunction "2_2") (pintype "passive"))
      (node (ref "C32") (pin "P$2") (pinfunction "2_P$2") (pintype "passive"))
      (node (ref "C33") (pin "P$2") (pinfunction "2_P$2") (pintype "passive"))
      (node (ref "C34") (pin "P$1") (pinfunction "1_P$1") (pintype "passive"))
      (node (ref "C35") (pin "P$1") (pinfunction "1_P$1") (pintype "passive"))
      (node (ref "C36") (pin "P$2") (pinfunction "2_P$2") (pintype "passive"))
      (node (ref "C37") (pin "P$2") (pinfunction "2_P$2") (pintype "passive"))
      (node (ref "C38") (pin "P$1") (pinfunction "1_P$1") (pintype "passive"))
      (node (ref "C39") (pin "P$2") (pinfunction "2_P$2") (pintype "passive"))
      (node (ref "C4") (pin "P$2") (pinfunction "2_P$2") (pintype "passive"))
      (node (ref "C40") (pin "P$2") (pinfunction "2_P$2") (pintype "passive"))
      (node (ref "C41") (pin "P$2") (pinfunction "2_P$2") (pintype "passive"))
      (node (ref "C42") (pin "P$2") (pinfunction "2_P$2") (pintype "passive"))
      (node (ref "C43") (pin "P$1") (pinfunction "1_P$1") (pintype "passive"))
      (node (ref "C5") (pin "P$2") (pinfunction "2_P$2") (pintype "passive"))
      (node (ref "C6") (pin "P$2") (pinfunction "2_P$2") (pintype "passive"))
      (node (ref "C7") (pin "P$2") (pinfunction "2_P$2") (pintype "passive"))
      (node (ref "C8") (pin "P$2") (pinfunction "2_P$2") (pintype "passive"))
      (node (ref "C9") (pin "P$2") (pinfunction "2_P$2") (pintype "passive"))
      (node (ref "J1") (pin "6") (pinfunction "SUPPLY_VOLTAGE_GROUND_6") (pintype "power_in"))
      (node (ref "J10") (pin "P$19") (pinfunction "P$19_P$19") (pintype "bidirectional"))
      (node (ref "J2") (pin "P$1") (pinfunction "P$1_P$1") (pintype "bidirectional"))
      (node (ref "J3") (pin "10") (pinfunction "10_10") (pintype "passive"))
      (node (ref "J3") (pin "6") (pinfunction "6_6") (pintype "passive"))
      (node (ref "J3") (pin "8") (pinfunction "8_8") (pintype "passive"))
      (node (ref "J6") (pin "GND") (pinfunction "GND_GND") (pintype "power_in"))
      (node (ref "J7") (pin "P$5") (pinfunction "GND_P$5") (pintype "bidirectional"))
      (node (ref "J8") (pin "P$1") (pinfunction "P$1_P$1") (pintype "bidirectional"))
      (node (ref "J9") (pin "10") (pinfunction "10_10") (pintype "passive"))
      (node (ref "J9") (pin "2") (pinfunction "2_2") (pintype "passive"))
      (node (ref "J9") (pin "4") (pinfunction "4_4") (pintype "passive"))
      (node (ref "J9") (pin "6") (pinfunction "6_6") (pintype "passive"))
      (node (ref "J9") (pin "8") (pinfunction "8_8") (pintype "passive"))
      (node (ref "LED1") (pin "2") (pinfunction "C_2") (pintype "passive"))
      (node (ref "R1") (pin "P$1") (pinfunction "1_P$1") (pintype "passive"))
      (node (ref "R21") (pin "P$1") (pinfunction "1_P$1") (pintype "passive"))
      (node (ref "R22") (pin "P$1") (pinfunction "1_P$1") (pintype "passive"))
      (node (ref "R23") (pin "P$1") (pinfunction "1_P$1") (pintype "passive"))
      (node (ref "R24") (pin "P$1") (pinfunction "1_P$1") (pintype "passive"))
      (node (ref "RJ1") (pin "10") (pinfunction "GLO_10") (pintype "bidirectional"))
      (node (ref "RJ1") (pin "8") (pinfunction "P8_8") (pintype "bidirectional"))
      (node (ref "U1") (pin "22") (pinfunction "GND_22") (pintype "power_in"))
      (node (ref "U1") (pin "25") (pinfunction "25_25") (pintype "passive"))
      (node (ref "U2") (pin "2") (pinfunction "GND_2") (pintype "input"))
      (node (ref "U3") (pin "111") (pinfunction "VSS(IO)5_111") (pintype "bidirectional"))
      (node (ref "U3") (pin "124") (pinfunction "VSS(IO)6_124") (pintype "bidirectional"))
      (node (ref "U3") (pin "139") (pinfunction "VSS(IO)7_139") (pintype "bidirectional"))
      (node (ref "U3") (pin "150") (pinfunction "VSS(IO)8_150") (pintype "bidirectional"))
      (node (ref "U3") (pin "153") (pinfunction "VREFL_153") (pintype "bidirectional"))
      (node (ref "U3") (pin "156") (pinfunction "AVSS0_156") (pintype "bidirectional"))
      (node (ref "U3") (pin "157") (pinfunction "VREFL0_157") (pintype "bidirectional"))
      (node (ref "U3") (pin "170") (pinfunction "VSS(IO)9_170") (pintype "bidirectional"))
      (node (ref "U3") (pin "22") (pinfunction "VSS1_22") (pintype "bidirectional"))
      (node (ref "U3") (pin "28") (pinfunction "AVSS_USBHS_28") (pintype "bidirectional"))
      (node (ref "U3") (pin "29") (pinfunction "PVSS_USBHS_29") (pintype "bidirectional"))
      (node (ref "U3") (pin "30") (pinfunction "VSS2_USBHS_30") (pintype "bidirectional"))
      (node (ref "U3") (pin "33") (pinfunction "VSS1_USBHS_33") (pintype "bidirectional"))
      (node (ref "U3") (pin "35") (pinfunction "VSSIO_35") (pintype "bidirectional"))
      (node (ref "U3") (pin "45") (pinfunction "VSS_USB_45") (pintype "bidirectional"))
      (node (ref "U3") (pin "60") (pinfunction "VSS(IO)2_60") (pintype "bidirectional"))
      (node (ref "U3") (pin "63") (pinfunction "VSS(IO/DCDC)_63") (pintype "bidirectional"))
      (node (ref "U3") (pin "66") (pinfunction "VCC_DCDC(IO/DCDC)_66") (pintype "bidirectional"))
      (node (ref "U3") (pin "83") (pinfunction "VSS(IO)3_83") (pintype "bidirectional"))
      (node (ref "U3") (pin "98") (pinfunction "VSS(IO)4_98") (pintype "bidirectional"))
      (node (ref "X1") (pin "2") (pinfunction "2_2") (pintype "bidirectional"))
      (node (ref "X1") (pin "4") (pinfunction "4_4") (pintype "bidirectional"))
      (node (ref "X2") (pin "2") (pinfunction "2_2") (pintype "bidirectional"))
      (node (ref "X2") (pin "4") (pinfunction "4_4") (pintype "bidirectional"))
    )
    (net (code "17") (name "GNDE") (class "Default")
      (node (ref "J1") (pin "S1") (pinfunction "SHIELD_S1") (pintype "passive"))
      (node (ref "J1") (pin "S2") (pinfunction "SHIELD_S2") (pintype "passive"))
      (node (ref "J1") (pin "S3") (pinfunction "SHIELD_S3") (pintype "passive"))
      (node (ref "J1") (pin "S4") (pinfunction "SHIELD_S4") (pintype "passive"))
      (node (ref "J2") (pin "P$4") (pinfunction "P$4_P$4") (pintype "bidirectional"))
      (node (ref "J6") (pin "SHLD1") (pinfunction "SHIELD_1_SHLD1") (pintype "bidirectional"))
      (node (ref "J6") (pin "SHLD2") (pinfunction "SHIELD_2_SHLD2") (pintype "bidirectional"))
      (node (ref "J7") (pin "P$6") (pinfunction "SHIELD1_P$6") (pintype "bidirectional"))
      (node (ref "J7") (pin "P$7") (pinfunction "SHIELD2_P$7") (pintype "bidirectional"))
      (node (ref "J7") (pin "P$8") (pinfunction "SHIELD3_P$8") (pintype "bidirectional"))
      (node (ref "J7") (pin "P$9") (pinfunction "SHIELD4_P$9") (pintype "bidirectional"))
      (node (ref "RJ1") (pin "13") (pinfunction "GNDE0_13") (pintype "bidirectional"))
      (node (ref "RJ1") (pin "14") (pinfunction "GNDE1_14") (pintype "bidirectional"))
    )
    (net (code "18") (name "ID") (class "Default")
      (node (ref "J7") (pin "P$4") (pinfunction "ID_P$4") (pintype "bidirectional"))
    )
    (net (code "19") (name "IIC_1_SCL") (class "Default")
      (node (ref "J8") (pin "P$5") (pinfunction "P$5_P$5") (pintype "bidirectional"))
      (node (ref "R14") (pin "P$2") (pinfunction "2_P$2") (pintype "passive"))
      (node (ref "U3") (pin "132") (pinfunction "P1_0_132") (pintype "bidirectional"))
    )
    (net (code "20") (name "IIC_1_SDA") (class "Default")
      (node (ref "J8") (pin "P$6") (pinfunction "P$6_P$6") (pintype "bidirectional"))
      (node (ref "R15") (pin "P$2") (pinfunction "2_P$2") (pintype "passive"))
      (node (ref "U3") (pin "131") (pinfunction "P1_1_131") (pintype "bidirectional"))
    )
    (net (code "21") (name "INT_MI_01") (class "Default")
      (node (ref "J8") (pin "P$39") (pinfunction "P$39_P$39") (pintype "bidirectional"))
      (node (ref "U3") (pin "87") (pinfunction "P3_1_87") (pintype "bidirectional"))
    )
    (net (code "22") (name "INT_MI_02") (class "Default")
      (node (ref "J8") (pin "P$40") (pinfunction "P$40_P$40") (pintype "bidirectional"))
      (node (ref "U3") (pin "86") (pinfunction "P3_2_86") (pintype "bidirectional"))
    )
    (net (code "23") (name "INT_MI_03") (class "Default")
      (node (ref "J8") (pin "P$9") (pinfunction "P$9_P$9") (pintype "bidirectional"))
      (node (ref "U3") (pin "128") (pinfunction "P1_4_128") (pintype "bidirectional"))
    )
    (net (code "24") (name "INT_MI_04") (class "Default")
      (node (ref "J8") (pin "P$10") (pinfunction "P$10_P$10") (pintype "bidirectional"))
      (node (ref "U3") (pin "127") (pinfunction "P1_5_127") (pintype "bidirectional"))
    )
    (net (code "25") (name "LED1{slash}SPEED") (class "Default")
      (node (ref "RJ1") (pin "11") (pinfunction "YLO_11") (pintype "bidirectional"))
      (node (ref "U1") (pin "23") (pinfunction "LED0/ANEN_SPEED_23") (pintype "bidirectional"))
    )
    (net (code "26") (name "NC") (class "Default")
      (node (ref "RJ1") (pin "7") (pinfunction "P7_7") (pintype "bidirectional"))
    )
    (net (code "27") (name "Net-(C8-1)") (class "Default")
      (node (ref "C8") (pin "P$1") (pinfunction "1_P$1") (pintype "passive"))
      (node (ref "C9") (pin "P$1") (pinfunction "1_P$1") (pintype "passive"))
      (node (ref "FB1") (pin "2") (pinfunction "P$2_2") (pintype "bidirectional"))
      (node (ref "U1") (pin "2") (pinfunction "VDDA_3.3_2") (pintype "power_in"))
    )
    (net (code "28") (name "Net-(C24-2)") (class "Default")
      (node (ref "C24") (pin "P$2") (pinfunction "2_P$2") (pintype "passive"))
      (node (ref "U3") (pin "148") (pinfunction "VCL2_148") (pintype "bidirectional"))
    )
    (net (code "29") (name "Net-(C28-1)") (class "Default")
      (node (ref "C28") (pin "P$1") (pinfunction "1_P$1") (pintype "passive"))
      (node (ref "J7") (pin "P$1") (pinfunction "VBUS_P$1") (pintype "bidirectional"))
      (node (ref "R16") (pin "P$2") (pinfunction "2_P$2") (pintype "passive"))
      (node (ref "R21") (pin "P$2") (pinfunction "2_P$2") (pintype "passive"))
    )
    (net (code "30") (name "Net-(C33-1)") (class "Default")
      (node (ref "C33") (pin "P$1") (pinfunction "1_P$1") (pintype "passive"))
      (node (ref "U3") (pin "19") (pinfunction "VCLO_19") (pintype "bidirectional"))
    )
    (net (code "31") (name "Net-(C42-1)") (class "Default")
      (node (ref "C42") (pin "P$1") (pinfunction "1_P$1") (pintype "passive"))
      (node (ref "U3") (pin "62") (pinfunction "VCL1_62") (pintype "bidirectional"))
    )
    (net (code "32") (name "Net-(J7-D+)") (class "Default")
      (node (ref "J7") (pin "P$3") (pinfunction "D+_P$3") (pintype "bidirectional"))
      (node (ref "R18") (pin "P$2") (pinfunction "2_P$2") (pintype "passive"))
    )
    (net (code "33") (name "Net-(J7-D-)") (class "Default")
      (node (ref "J7") (pin "P$2") (pinfunction "D-_P$2") (pintype "bidirectional"))
      (node (ref "R17") (pin "P$2") (pinfunction "2_P$2") (pintype "passive"))
    )
    (net (code "34") (name "Net-(LED1-A)") (class "Default")
      (node (ref "LED1") (pin "1") (pinfunction "A_1") (pintype "passive"))
      (node (ref "R5") (pin "P$1") (pinfunction "1_P$1") (pintype "passive"))
    )
    (net (code "35") (name "Net-(R22-2)") (class "Default")
      (node (ref "R22") (pin "P$2") (pinfunction "2_P$2") (pintype "passive"))
      (node (ref "U3") (pin "27") (pinfunction "USBHS_RREF_27") (pintype "bidirectional"))
    )
    (net (code "36") (name "Net-(R23-2)") (class "Default")
      (node (ref "R23") (pin "P$2") (pinfunction "2_P$2") (pintype "passive"))
      (node (ref "U3") (pin "64") (pinfunction "VLO1(DCDC)_64") (pintype "bidirectional"))
    )
    (net (code "37") (name "Net-(R24-2)") (class "Default")
      (node (ref "R24") (pin "P$2") (pinfunction "2_P$2") (pintype "passive"))
      (node (ref "U3") (pin "65") (pinfunction "VLO2(DCDC)_65") (pintype "bidirectional"))
    )
    (net (code "38") (name "P0_00") (class "Default")
      (node (ref "J4") (pin "P$2") (pinfunction "P$2_P$2") (pintype "bidirectional"))
      (node (ref "U3") (pin "169") (pinfunction "P0_0/AN0\\00_169") (pintype "bidirectional"))
    )
    (net (code "39") (name "P0_01") (class "Default")
      (node (ref "J4") (pin "P$1") (pinfunction "P$1_P$1") (pintype "bidirectional"))
      (node (ref "U3") (pin "168") (pinfunction "P0_1/AN001_168") (pintype "bidirectional"))
    )
    (net (code "40") (name "P0_02") (class "Default")
      (node (ref "J5") (pin "1") (pinfunction "1_1") (pintype "passive"))
      (node (ref "U3") (pin "167") (pinfunction "P0_2/AN002_167") (pintype "bidirectional"))
    )
    (net (code "41") (name "P0_03") (class "Default")
      (node (ref "J5") (pin "3") (pinfunction "3_3") (pintype "passive"))
      (node (ref "U3") (pin "166") (pinfunction "P0_3/PGAVSS000_166") (pintype "bidirectional"))
    )
    (net (code "42") (name "P0_04") (class "Default")
      (node (ref "J5") (pin "5") (pinfunction "5_5") (pintype "passive"))
      (node (ref "U3") (pin "165") (pinfunction "P0_4/AN100_165") (pintype "bidirectional"))
    )
    (net (code "43") (name "P0_05") (class "Default")
      (node (ref "J5") (pin "7") (pinfunction "7_7") (pintype "passive"))
      (node (ref "U3") (pin "164") (pinfunction "P0_5/AN101_164") (pintype "bidirectional"))
    )
    (net (code "44") (name "P0_06") (class "Default")
      (node (ref "J5") (pin "9") (pinfunction "9_9") (pintype "passive"))
      (node (ref "U3") (pin "163") (pinfunction "P0_6/AN102_163") (pintype "bidirectional"))
    )
    (net (code "45") (name "P0_07") (class "Default")
      (node (ref "J5") (pin "10") (pinfunction "10_10") (pintype "passive"))
      (node (ref "U3") (pin "162") (pinfunction "P0_7/PGVSS100_162") (pintype "bidirectional"))
    )
    (net (code "46") (name "P0_08") (class "Default")
      (node (ref "J5") (pin "8") (pinfunction "8_8") (pintype "passive"))
      (node (ref "U3") (pin "161") (pinfunction "P0_8/AN003_161") (pintype "bidirectional"))
    )
    (net (code "47") (name "P0_09") (class "Default")
      (node (ref "J5") (pin "6") (pinfunction "6_6") (pintype "passive"))
      (node (ref "U3") (pin "160") (pinfunction "P0_9/AN004_160") (pintype "bidirectional"))
    )
    (net (code "48") (name "P0_14") (class "Default")
      (node (ref "J5") (pin "4") (pinfunction "4_4") (pintype "passive"))
      (node (ref "U3") (pin "152") (pinfunction "P0_14/DA0/AN005/AN105_152") (pintype "bidirectional"))
    )
    (net (code "49") (name "P0_15") (class "Default")
      (node (ref "J5") (pin "2") (pinfunction "2_2") (pintype "passive"))
      (node (ref "U3") (pin "151") (pinfunction "P0_15/DA1/AN006/AN106_151") (pintype "bidirectional"))
    )
    (net (code "50") (name "P1_02") (class "Default")
      (node (ref "J8") (pin "P$7") (pinfunction "P$7_P$7") (pintype "bidirectional"))
      (node (ref "U3") (pin "130") (pinfunction "P1_2_130") (pintype "bidirectional"))
    )
    (net (code "51") (name "P1_03") (class "Default")
      (node (ref "J8") (pin "P$8") (pinfunction "P$8_P$8") (pintype "bidirectional"))
      (node (ref "U3") (pin "129") (pinfunction "P1_3_129") (pintype "bidirectional"))
    )
    (net (code "52") (name "P1_06") (class "Default")
      (node (ref "J8") (pin "P$11") (pinfunction "P$11_P$11") (pintype "bidirectional"))
      (node (ref "U3") (pin "126") (pinfunction "P1_6_126") (pintype "bidirectional"))
    )
    (net (code "53") (name "P1_07") (class "Default")
      (node (ref "J8") (pin "P$12") (pinfunction "P$12_P$12") (pintype "bidirectional"))
      (node (ref "U3") (pin "125") (pinfunction "P1_7_125") (pintype "bidirectional"))
    )
    (net (code "54") (name "P1_11") (class "Default")
      (node (ref "J8") (pin "P$38") (pinfunction "P$38_P$38") (pintype "bidirectional"))
      (node (ref "U3") (pin "92") (pinfunction "P1_11_92") (pintype "bidirectional"))
    )
    (net (code "55") (name "P1_12") (class "Default")
      (node (ref "J8") (pin "P$37") (pinfunction "P$37_P$37") (pintype "bidirectional"))
      (node (ref "U3") (pin "93") (pinfunction "P1_12_93") (pintype "bidirectional"))
    )
    (net (code "56") (name "P1_13") (class "Default")
      (node (ref "J8") (pin "P$36") (pinfunction "P$36_P$36") (pintype "bidirectional"))
      (node (ref "U3") (pin "94") (pinfunction "P1_13_94") (pintype "bidirectional"))
    )
    (net (code "57") (name "P1_14") (class "Default")
      (node (ref "J8") (pin "P$35") (pinfunction "P$35_P$35") (pintype "bidirectional"))
      (node (ref "U3") (pin "95") (pinfunction "P1_14_95") (pintype "bidirectional"))
    )
    (net (code "58") (name "P1_15") (class "Default")
      (node (ref "J8") (pin "P$34") (pinfunction "P$34_P$34") (pintype "bidirectional"))
      (node (ref "U3") (pin "96") (pinfunction "P1_15_96") (pintype "bidirectional"))
    )
    (net (code "59") (name "P2_00") (class "Default")
      (node (ref "J10") (pin "P$13") (pinfunction "P$13_P$13") (pintype "bidirectional"))
      (node (ref "U3") (pin "69") (pinfunction "P2_0(INPUT_ONLY)_69") (pintype "bidirectional"))
    )
    (net (code "60") (name "P2_01") (class "Default")
      (node (ref "J10") (pin "P$14") (pinfunction "P$14_P$14") (pintype "bidirectional"))
      (node (ref "U3") (pin "68") (pinfunction "P2_1/MD_68") (pintype "bidirectional"))
    )
    (net (code "61") (name "P2_02") (class "Default")
      (node (ref "J4") (pin "P$9") (pinfunction "P$9_P$9") (pintype "bidirectional"))
      (node (ref "U3") (pin "54") (pinfunction "P2_2_54") (pintype "bidirectional"))
    )
    (net (code "62") (name "P2_03") (class "Default")
      (node (ref "J9") (pin "1") (pinfunction "1_1") (pintype "passive"))
      (node (ref "U3") (pin "53") (pinfunction "P2_3_53") (pintype "bidirectional"))
    )
    (net (code "63") (name "P2_04") (class "Default")
      (node (ref "J9") (pin "3") (pinfunction "3_3") (pintype "passive"))
      (node (ref "U3") (pin "52") (pinfunction "P2_4_52") (pintype "bidirectional"))
    )
    (net (code "64") (name "P2_05") (class "Default")
      (node (ref "J9") (pin "5") (pinfunction "5_5") (pintype "passive"))
      (node (ref "U3") (pin "51") (pinfunction "P2_5_51") (pintype "bidirectional"))
    )
    (net (code "65") (name "P2_06") (class "Default")
      (node (ref "J9") (pin "7") (pinfunction "7_7") (pintype "passive"))
      (node (ref "U3") (pin "50") (pinfunction "P2_6_50") (pintype "bidirectional"))
    )
    (net (code "66") (name "P2_07") (class "Default")
      (node (ref "J9") (pin "9") (pinfunction "9_9") (pintype "passive"))
      (node (ref "U3") (pin "49") (pinfunction "P2_7_49") (pintype "bidirectional"))
    )
    (net (code "67") (name "P3_03") (class "Default")
      (node (ref "J10") (pin "P$2") (pinfunction "P$2_P$2") (pintype "bidirectional"))
      (node (ref "U3") (pin "85") (pinfunction "P3_3_85") (pintype "bidirectional"))
    )
    (net (code "68") (name "P3_04") (class "Default")
      (node (ref "J10") (pin "P$4") (pinfunction "P$4_P$4") (pintype "bidirectional"))
      (node (ref "U3") (pin "82") (pinfunction "P3_4_82") (pintype "bidirectional"))
    )
    (net (code "69") (name "P3_05") (class "Default")
      (node (ref "J10") (pin "P$6") (pinfunction "P$6_P$6") (pintype "bidirectional"))
      (node (ref "U3") (pin "81") (pinfunction "P3_5_81") (pintype "bidirectional"))
    )
    (net (code "70") (name "P3_06") (class "Default")
      (node (ref "J10") (pin "P$1") (pinfunction "P$1_P$1") (pintype "bidirectional"))
      (node (ref "U3") (pin "80") (pinfunction "P3_6_80") (pintype "bidirectional"))
    )
    (net (code "71") (name "P3_07") (class "Default")
      (node (ref "J10") (pin "P$3") (pinfunction "P$3_P$3") (pintype "bidirectional"))
      (node (ref "U3") (pin "79") (pinfunction "P3_7_79") (pintype "bidirectional"))
    )
    (net (code "72") (name "P3_09") (class "Default")
      (node (ref "J10") (pin "P$5") (pinfunction "P$5_P$5") (pintype "bidirectional"))
      (node (ref "U3") (pin "77") (pinfunction "P3_9_77") (pintype "bidirectional"))
    )
    (net (code "73") (name "P3_10") (class "Default")
      (node (ref "J10") (pin "P$7") (pinfunction "P$7_P$7") (pintype "bidirectional"))
      (node (ref "U3") (pin "76") (pinfunction "P3_10_76") (pintype "bidirectional"))
    )
    (net (code "74") (name "P3_11") (class "Default")
      (node (ref "J10") (pin "P$8") (pinfunction "P$8_P$8") (pintype "bidirectional"))
      (node (ref "U3") (pin "75") (pinfunction "P3_11_75") (pintype "bidirectional"))
    )
    (net (code "75") (name "P3_12") (class "Default")
      (node (ref "J10") (pin "P$9") (pinfunction "P$9_P$9") (pintype "bidirectional"))
      (node (ref "U3") (pin "74") (pinfunction "P3_12_74") (pintype "bidirectional"))
    )
    (net (code "76") (name "P3_13") (class "Default")
      (node (ref "J10") (pin "P$20") (pinfunction "P$20_P$20") (pintype "bidirectional"))
      (node (ref "U3") (pin "55") (pinfunction "P3_13_55") (pintype "bidirectional"))
    )
    (net (code "77") (name "P3_14") (class "Default")
      (node (ref "J10") (pin "P$17") (pinfunction "P$17_P$17") (pintype "bidirectional"))
      (node (ref "U3") (pin "56") (pinfunction "P3_14_56") (pintype "bidirectional"))
    )
    (net (code "78") (name "P3_15") (class "Default")
      (node (ref "J10") (pin "P$18") (pinfunction "P$18_P$18") (pintype "bidirectional"))
      (node (ref "U3") (pin "57") (pinfunction "P3_15_57") (pintype "bidirectional"))
    )
    (net (code "79") (name "P4_00") (class "Default")
      (node (ref "J4") (pin "P$7") (pinfunction "P$7_P$7") (pintype "bidirectional"))
      (node (ref "U3") (pin "1") (pinfunction "P4_0_1") (pintype "bidirectional"))
    )
    (net (code "80") (name "P4_01") (class "Default")
      (node (ref "J4") (pin "P$8") (pinfunction "P$8_P$8") (pintype "bidirectional"))
      (node (ref "U3") (pin "2") (pinfunction "P4_1_2") (pintype "bidirectional"))
    )
    (net (code "81") (name "P4_02") (class "Default")
      (node (ref "U3") (pin "3") (pinfunction "P4_2_3") (pintype "bidirectional"))
    )
    (net (code "82") (name "P4_08") (class "Default")
      (node (ref "J4") (pin "P$20") (pinfunction "P$20_P$20") (pintype "bidirectional"))
      (node (ref "U3") (pin "43") (pinfunction "P4_8_43") (pintype "bidirectional"))
    )
    (net (code "83") (name "P4_09") (class "Default")
      (node (ref "J4") (pin "P$19") (pinfunction "P$19_P$19") (pintype "bidirectional"))
      (node (ref "U3") (pin "42") (pinfunction "P4_9_42") (pintype "bidirectional"))
    )
    (net (code "84") (name "P4_10") (class "Default")
      (node (ref "J4") (pin "P$18") (pinfunction "P$18_P$18") (pintype "bidirectional"))
      (node (ref "U3") (pin "41") (pinfunction "P4_10_41") (pintype "bidirectional"))
    )
    (net (code "85") (name "P4_11") (class "Default")
      (node (ref "J4") (pin "P$17") (pinfunction "P$17_P$17") (pintype "bidirectional"))
      (node (ref "U3") (pin "40") (pinfunction "P4_11_40") (pintype "bidirectional"))
    )
    (net (code "86") (name "P4_12") (class "Default")
      (node (ref "J4") (pin "P$16") (pinfunction "P$16_P$16") (pintype "bidirectional"))
      (node (ref "U3") (pin "39") (pinfunction "P4_12_39") (pintype "bidirectional"))
    )
    (net (code "87") (name "P4_13") (class "Default")
      (node (ref "J4") (pin "P$15") (pinfunction "P$15_P$15") (pintype "bidirectional"))
      (node (ref "U3") (pin "38") (pinfunction "P4_13_38") (pintype "bidirectional"))
    )
    (net (code "88") (name "P4_14") (class "Default")
      (node (ref "J4") (pin "P$14") (pinfunction "P$14_P$14") (pintype "bidirectional"))
      (node (ref "U3") (pin "37") (pinfunction "P4_14_37") (pintype "bidirectional"))
    )
    (net (code "89") (name "P4_15") (class "Default")
      (node (ref "J4") (pin "P$13") (pinfunction "P$13_P$13") (pintype "bidirectional"))
      (node (ref "U3") (pin "36") (pinfunction "P4_15_36") (pintype "bidirectional"))
    )
    (net (code "90") (name "P5_11") (class "Default")
      (node (ref "J4") (pin "P$6") (pinfunction "P$6_P$6") (pintype "bidirectional"))
      (node (ref "U3") (pin "176") (pinfunction "P5_11_176") (pintype "bidirectional"))
    )
    (net (code "91") (name "P5_12") (class "Default")
      (node (ref "J4") (pin "P$5") (pinfunction "P$5_P$5") (pintype "bidirectional"))
      (node (ref "U3") (pin "175") (pinfunction "P5_12_175") (pintype "bidirectional"))
    )
    (net (code "92") (name "P5_13") (class "Default")
      (node (ref "J4") (pin "P$4") (pinfunction "P$4_P$4") (pintype "bidirectional"))
      (node (ref "U3") (pin "174") (pinfunction "P5_13_174") (pintype "bidirectional"))
    )
    (net (code "93") (name "P6_00") (class "Default")
      (node (ref "J8") (pin "P$13") (pinfunction "P$13_P$13") (pintype "bidirectional"))
      (node (ref "U3") (pin "122") (pinfunction "P6_0_122") (pintype "bidirectional"))
    )
    (net (code "94") (name "P6_01") (class "Default")
      (node (ref "J8") (pin "P$14") (pinfunction "P$14_P$14") (pintype "bidirectional"))
      (node (ref "U3") (pin "121") (pinfunction "P6_1_121") (pintype "bidirectional"))
    )
    (net (code "95") (name "P6_02") (class "Default")
      (node (ref "J8") (pin "P$15") (pinfunction "P$15_P$15") (pintype "bidirectional"))
      (node (ref "U3") (pin "120") (pinfunction "P6_2_120") (pintype "bidirectional"))
    )
    (net (code "96") (name "P6_03") (class "Default")
      (node (ref "J8") (pin "P$16") (pinfunction "P$16_P$16") (pintype "bidirectional"))
      (node (ref "U3") (pin "119") (pinfunction "P6_3_119") (pintype "bidirectional"))
    )
    (net (code "97") (name "P6_04") (class "Default")
      (node (ref "J8") (pin "P$17") (pinfunction "P$17_P$17") (pintype "bidirectional"))
      (node (ref "U3") (pin "118") (pinfunction "P6_4_118") (pintype "bidirectional"))
    )
    (net (code "98") (name "P6_05") (class "Default")
      (node (ref "J8") (pin "P$18") (pinfunction "P$18_P$18") (pintype "bidirectional"))
      (node (ref "U3") (pin "117") (pinfunction "P6_5_117") (pintype "bidirectional"))
    )
    (net (code "99") (name "P6_06") (class "Default")
      (node (ref "J8") (pin "P$19") (pinfunction "P$19_P$19") (pintype "bidirectional"))
      (node (ref "U3") (pin "116") (pinfunction "P6_6_116") (pintype "bidirectional"))
    )
    (net (code "100") (name "P6_07") (class "Default")
      (node (ref "J8") (pin "P$20") (pinfunction "P$20_P$20") (pintype "bidirectional"))
      (node (ref "U3") (pin "115") (pinfunction "P6_7_115") (pintype "bidirectional"))
    )
    (net (code "101") (name "P6_08") (class "Default")
      (node (ref "J8") (pin "P$33") (pinfunction "P$33_P$33") (pintype "bidirectional"))
      (node (ref "U3") (pin "99") (pinfunction "P6_8_99") (pintype "bidirectional"))
    )
    (net (code "102") (name "P6_09") (class "Default")
      (node (ref "J8") (pin "P$32") (pinfunction "P$32_P$32") (pintype "bidirectional"))
      (node (ref "U3") (pin "100") (pinfunction "P6_9_100") (pintype "bidirectional"))
    )
    (net (code "103") (name "P6_10") (class "Default")
      (node (ref "J8") (pin "P$31") (pinfunction "P$31_P$31") (pintype "bidirectional"))
      (node (ref "U3") (pin "101") (pinfunction "P6_10_101") (pintype "bidirectional"))
    )
    (net (code "104") (name "P6_11") (class "Default")
      (node (ref "J8") (pin "P$30") (pinfunction "P$30_P$30") (pintype "bidirectional"))
      (node (ref "U3") (pin "102") (pinfunction "P6_11_102") (pintype "bidirectional"))
    )
    (net (code "105") (name "P6_12") (class "Default")
      (node (ref "J8") (pin "P$29") (pinfunction "P$29_P$29") (pintype "bidirectional"))
      (node (ref "U3") (pin "103") (pinfunction "P6_12_103") (pintype "bidirectional"))
    )
    (net (code "106") (name "P6_13") (class "Default")
      (node (ref "J8") (pin "P$28") (pinfunction "P$28_P$28") (pintype "bidirectional"))
      (node (ref "U3") (pin "104") (pinfunction "P6_13_104") (pintype "bidirectional"))
    )
    (net (code "107") (name "P6_14") (class "Default")
      (node (ref "J8") (pin "P$27") (pinfunction "P$27_P$27") (pintype "bidirectional"))
      (node (ref "U3") (pin "105") (pinfunction "P6_14_105") (pintype "bidirectional"))
    )
    (net (code "108") (name "P6_15") (class "Default")
      (node (ref "J8") (pin "P$26") (pinfunction "P$26_P$26") (pintype "bidirectional"))
      (node (ref "U3") (pin "106") (pinfunction "P6_15_106") (pintype "bidirectional"))
    )
    (net (code "109") (name "P7_06") (class "Default")
      (node (ref "J4") (pin "P$10") (pinfunction "P$10_P$10") (pintype "bidirectional"))
      (node (ref "U3") (pin "14") (pinfunction "P7_6_14") (pintype "bidirectional"))
    )
    (net (code "110") (name "P7_07") (class "Default")
      (node (ref "J4") (pin "P$11") (pinfunction "P$11_P$11") (pintype "bidirectional"))
      (node (ref "U3") (pin "15") (pinfunction "P7_7_15") (pintype "bidirectional"))
    )
    (net (code "111") (name "P8_00") (class "Default")
      (node (ref "J8") (pin "P$4") (pinfunction "P$4_P$4") (pintype "bidirectional"))
      (node (ref "U3") (pin "133") (pinfunction "P8_0_133") (pintype "bidirectional"))
    )
    (net (code "112") (name "P8_01") (class "Default")
      (node (ref "J8") (pin "P$3") (pinfunction "P$3_P$3") (pintype "bidirectional"))
      (node (ref "U3") (pin "134") (pinfunction "P8_1_134") (pintype "bidirectional"))
    )
    (net (code "113") (name "P8_02") (class "Default")
      (node (ref "J8") (pin "P$2") (pinfunction "P$2_P$2") (pintype "bidirectional"))
      (node (ref "U3") (pin "135") (pinfunction "P8_2_135") (pintype "bidirectional"))
    )
    (net (code "114") (name "P8_03") (class "Default")
      (node (ref "U3") (pin "136") (pinfunction "P8_3_136") (pintype "bidirectional"))
    )
    (net (code "115") (name "P8_04") (class "Default")
      (node (ref "U3") (pin "137") (pinfunction "P8_4_137") (pintype "bidirectional"))
    )
    (net (code "116") (name "P8_05") (class "Default")
      (node (ref "J4") (pin "P$3") (pinfunction "P$3_P$3") (pintype "bidirectional"))
      (node (ref "U3") (pin "173") (pinfunction "P8_5_173") (pintype "bidirectional"))
    )
    (net (code "117") (name "P9_00") (class "Default")
      (node (ref "J10") (pin "P$16") (pinfunction "P$16_P$16") (pintype "bidirectional"))
      (node (ref "U3") (pin "58") (pinfunction "P9_0_58") (pintype "bidirectional"))
    )
    (net (code "118") (name "P9_01") (class "Default")
      (node (ref "J10") (pin "P$15") (pinfunction "P$15_P$15") (pintype "bidirectional"))
      (node (ref "U3") (pin "59") (pinfunction "P9_1_59") (pintype "bidirectional"))
    )
    (net (code "119") (name "P9_05") (class "Default")
      (node (ref "J10") (pin "P$10") (pinfunction "P$10_P$10") (pintype "bidirectional"))
      (node (ref "U3") (pin "73") (pinfunction "P9_5_73") (pintype "bidirectional"))
    )
    (net (code "120") (name "P9_06") (class "Default")
      (node (ref "J10") (pin "P$11") (pinfunction "P$11_P$11") (pintype "bidirectional"))
      (node (ref "U3") (pin "72") (pinfunction "P9_6_72") (pintype "bidirectional"))
    )
    (net (code "121") (name "P9_07") (class "Default")
      (node (ref "J10") (pin "P$12") (pinfunction "P$12_P$12") (pintype "bidirectional"))
      (node (ref "U3") (pin "71") (pinfunction "P9_7_71") (pintype "bidirectional"))
    )
    (net (code "122") (name "P9_08") (class "Default")
      (node (ref "U3") (pin "70") (pinfunction "P9_8_70") (pintype "bidirectional"))
    )
    (net (code "123") (name "PA_00") (class "Default")
      (node (ref "J8") (pin "P$21") (pinfunction "P$21_P$21") (pintype "bidirectional"))
      (node (ref "U3") (pin "114") (pinfunction "PA_0_114") (pintype "bidirectional"))
    )
    (net (code "124") (name "PA_01") (class "Default")
      (node (ref "J8") (pin "P$22") (pinfunction "P$22_P$22") (pintype "bidirectional"))
      (node (ref "U3") (pin "113") (pinfunction "PA_1_113") (pintype "bidirectional"))
    )
    (net (code "125") (name "PA_08") (class "Default")
      (node (ref "J8") (pin "P$25") (pinfunction "P$25_P$25") (pintype "bidirectional"))
      (node (ref "U3") (pin "107") (pinfunction "PA_8_107") (pintype "bidirectional"))
    )
    (net (code "126") (name "PA_09") (class "Default")
      (node (ref "J8") (pin "P$24") (pinfunction "P$24_P$24") (pintype "bidirectional"))
      (node (ref "U3") (pin "108") (pinfunction "PA_9_108") (pintype "bidirectional"))
    )
    (net (code "127") (name "PA_10") (class "Default")
      (node (ref "J8") (pin "P$23") (pinfunction "P$23_P$23") (pintype "bidirectional"))
      (node (ref "U3") (pin "109") (pinfunction "PA_10_109") (pintype "bidirectional"))
    )
    (net (code "128") (name "PB_00") (class "Default")
      (node (ref "J4") (pin "P$12") (pinfunction "P$12_P$12") (pintype "bidirectional"))
      (node (ref "U3") (pin "16") (pinfunction "PB_0_16") (pintype "bidirectional"))
    )
    (net (code "129") (name "R51") (class "Default")
      (node (ref "R7") (pin "P$1") (pinfunction "1_P$1") (pintype "passive"))
      (node (ref "RJ1") (pin "12") (pinfunction "YHI_12") (pintype "bidirectional"))
    )
    (net (code "130") (name "R52") (class "Default")
      (node (ref "R8") (pin "P$1") (pinfunction "1_P$1") (pintype "passive"))
      (node (ref "RJ1") (pin "9") (pinfunction "GHI_9") (pintype "bidirectional"))
    )
    (net (code "131") (name "RESET") (class "Default")
      (node (ref "C16") (pin "P$1") (pinfunction "1_P$1") (pintype "passive"))
      (node (ref "J3") (pin "9") (pinfunction "9_9") (pintype "passive"))
      (node (ref "R13") (pin "P$1") (pinfunction "1_P$1") (pintype "passive"))
      (node (ref "U3") (pin "67") (pinfunction "RES#_67") (pintype "bidirectional"))
    )
    (net (code "132") (name "REXT") (class "Default")
      (node (ref "C3") (pin "P$1") (pinfunction "1_P$1") (pintype "passive"))
      (node (ref "R1") (pin "P$2") (pinfunction "2_P$2") (pintype "passive"))
      (node (ref "U1") (pin "9") (pinfunction "REXT_9") (pintype "input"))
    )
    (net (code "133") (name "RXD0") (class "Default")
      (node (ref "R10") (pin "P$2") (pinfunction "2_P$2") (pintype "passive"))
      (node (ref "U1") (pin "13") (pinfunction "RXD0_13") (pintype "bidirectional"))
    )
    (net (code "134") (name "RXD1") (class "Default")
      (node (ref "R9") (pin "P$2") (pinfunction "2_P$2") (pintype "passive"))
      (node (ref "U1") (pin "12") (pinfunction "RXD1_12") (pintype "bidirectional"))
    )
    (net (code "135") (name "RXER") (class "Default")
      (node (ref "R11") (pin "P$2") (pinfunction "2_P$2") (pintype "passive"))
      (node (ref "U1") (pin "17") (pinfunction "RXER_17") (pintype "bidirectional"))
    )
    (net (code "136") (name "RXM") (class "Default")
      (node (ref "RJ1") (pin "6") (pinfunction "RD-_6") (pintype "bidirectional"))
      (node (ref "U1") (pin "3") (pinfunction "RXM_3") (pintype "bidirectional"))
    )
    (net (code "137") (name "RXP") (class "Default")
      (node (ref "RJ1") (pin "3") (pinfunction "RD+_3") (pintype "bidirectional"))
      (node (ref "U1") (pin "4") (pinfunction "RXP_4") (pintype "bidirectional"))
    )
    (net (code "138") (name "SD1_CD") (class "Default")
      (node (ref "J1") (pin "10") (pinfunction "CD_SWITCH2_10") (pintype "bidirectional"))
      (node (ref "U3") (pin "146") (pinfunction "P5_6/AN019_146") (pintype "bidirectional"))
    )
    (net (code "139") (name "SD1_CLK") (class "Default")
      (node (ref "J1") (pin "5") (pinfunction "CLOCK_5") (pintype "bidirectional"))
      (node (ref "U3") (pin "140") (pinfunction "P5_0/AN016_140") (pintype "bidirectional"))
    )
    (net (code "140") (name "SD1_CMD") (class "Default")
      (node (ref "J1") (pin "3") (pinfunction "COMMAND/RESPONSE_3") (pintype "bidirectional"))
      (node (ref "U3") (pin "141") (pinfunction "P5_1/AN116_141") (pintype "bidirectional"))
    )
    (net (code "141") (name "SD1_DAT0") (class "Default")
      (node (ref "J1") (pin "7") (pinfunction "DATA_LINE[BIT_0]_7") (pintype "bidirectional"))
      (node (ref "U3") (pin "142") (pinfunction "P5_2/AN017_142") (pintype "bidirectional"))
    )
    (net (code "142") (name "SD1_DAT1") (class "Default")
      (node (ref "J1") (pin "8") (pinfunction "DATA_LINE[BIT_1]_8") (pintype "bidirectional"))
      (node (ref "U3") (pin "143") (pinfunction "P5_3/AN117_143") (pintype "bidirectional"))
    )
    (net (code "143") (name "SD1_DAT2") (class "Default")
      (node (ref "J1") (pin "1") (pinfunction "DATA_LINE[BIT_2]_1") (pintype "bidirectional"))
      (node (ref "U3") (pin "144") (pinfunction "P5_4/AN018_144") (pintype "bidirectional"))
    )
    (net (code "144") (name "SD1_DAT3") (class "Default")
      (node (ref "J1") (pin "2") (pinfunction "CARD_DETECT/DATA_LINE[BIT_3]_2") (pintype "bidirectional"))
      (node (ref "U3") (pin "145") (pinfunction "P5_5/AN118_145") (pintype "bidirectional"))
    )
    (net (code "145") (name "SD1_WP") (class "Default")
      (node (ref "J1") (pin "9") (pinfunction "CD_SWITCH1_9") (pintype "bidirectional"))
      (node (ref "U3") (pin "147") (pinfunction "P5_7/AN119_147") (pintype "bidirectional"))
    )
    (net (code "146") (name "TCK") (class "Default")
      (node (ref "J3") (pin "7") (pinfunction "7_7") (pintype "passive"))
      (node (ref "U3") (pin "88") (pinfunction "P3_0_88") (pintype "bidirectional"))
    )
    (net (code "147") (name "TDI") (class "Default")
      (node (ref "J3") (pin "1") (pinfunction "1_1") (pintype "passive"))
      (node (ref "U3") (pin "91") (pinfunction "P1_10_91") (pintype "bidirectional"))
    )
    (net (code "148") (name "TDO") (class "Default")
      (node (ref "J3") (pin "3") (pinfunction "3_3") (pintype "passive"))
      (node (ref "U3") (pin "90") (pinfunction "P1_9_90") (pintype "bidirectional"))
    )
    (net (code "149") (name "TMS") (class "Default")
      (node (ref "J3") (pin "5") (pinfunction "5_5") (pintype "passive"))
      (node (ref "U3") (pin "89") (pinfunction "P1_8_89") (pintype "bidirectional"))
    )
    (net (code "150") (name "TXM") (class "Default")
      (node (ref "RJ1") (pin "2") (pinfunction "TD-_2") (pintype "bidirectional"))
      (node (ref "U1") (pin "5") (pinfunction "TXM_5") (pintype "bidirectional"))
    )
    (net (code "151") (name "TXP") (class "Default")
      (node (ref "RJ1") (pin "1") (pinfunction "TD+_1") (pintype "bidirectional"))
      (node (ref "U1") (pin "6") (pinfunction "TXP_6") (pintype "bidirectional"))
    )
    (net (code "152") (name "USBHS_FAULT") (class "Default")
      (node (ref "R19") (pin "P$1") (pinfunction "1_P$1") (pintype "passive"))
      (node (ref "U2") (pin "3") (pinfunction "FLG_3") (pintype "input"))
      (node (ref "U3") (pin "78") (pinfunction "P3_8_78") (pintype "bidirectional"))
    )
    (net (code "153") (name "USBHS_N") (class "Default")
      (node (ref "J6") (pin "D-") (pinfunction "D-_D-") (pintype "bidirectional"))
      (node (ref "U3") (pin "31") (pinfunction "USBHS_DM_31") (pintype "bidirectional"))
    )
    (net (code "154") (name "USBHS_P") (class "Default")
      (node (ref "J6") (pin "D+") (pinfunction "D+_D+") (pintype "bidirectional"))
      (node (ref "U3") (pin "32") (pinfunction "USBHS_DP_32") (pintype "bidirectional"))
    )
    (net (code "155") (name "USBHS_VBUS") (class "Default")
      (node (ref "C29") (pin "P$1") (pinfunction "1_P$1") (pintype "passive"))
      (node (ref "C31") (pin "1") (pinfunction "1_1") (pintype "passive"))
      (node (ref "J6") (pin "VBUS") (pinfunction "VBUS_VBUS") (pintype "power_in"))
      (node (ref "U2") (pin "5") (pinfunction "OUT_5") (pintype "input"))
      (node (ref "U3") (pin "17") (pinfunction "PB_1_17") (pintype "bidirectional"))
    )
    (net (code "156") (name "USBHS_VBUSEN") (class "Default")
      (node (ref "R20") (pin "P$1") (pinfunction "1_P$1") (pintype "passive"))
      (node (ref "U2") (pin "1") (pinfunction "EN_1") (pintype "input"))
    )
    (net (code "157") (name "USB_N") (class "Default")
      (node (ref "R17") (pin "P$1") (pinfunction "1_P$1") (pintype "passive"))
      (node (ref "U3") (pin "46") (pinfunction "USB_DM_46") (pintype "bidirectional"))
    )
    (net (code "158") (name "USB_P") (class "Default")
      (node (ref "R18") (pin "P$1") (pinfunction "1_P$1") (pintype "passive"))
      (node (ref "U3") (pin "47") (pinfunction "USB_DP_47") (pintype "bidirectional"))
    )
    (net (code "159") (name "USB_VBUS_B") (class "Default")
      (node (ref "R16") (pin "P$1") (pinfunction "1_P$1") (pintype "passive"))
      (node (ref "U3") (pin "44") (pinfunction "P4_7_44") (pintype "bidirectional"))
    )
    (net (code "160") (name "VCL_F(FLASH)") (class "Default")
      (node (ref "C34") (pin "P$2") (pinfunction "2_P$2") (pintype "passive"))
      (node (ref "U3") (pin "112") (pinfunction "VCL_F(FLASH)_112") (pintype "bidirectional"))
    )
    (net (code "161") (name "VDD") (class "Default")
      (node (ref "C14") (pin "P$1") (pinfunction "1_P$1") (pintype "passive"))
      (node (ref "C15") (pin "P$1") (pinfunction "1_P$1") (pintype "passive"))
      (node (ref "C19") (pin "P$2") (pinfunction "2_P$2") (pintype "passive"))
      (node (ref "C20") (pin "P$2") (pinfunction "2_P$2") (pintype "passive"))
      (node (ref "C21") (pin "P$2") (pinfunction "2_P$2") (pintype "passive"))
      (node (ref "C22") (pin "P$2") (pinfunction "2_P$2") (pintype "passive"))
      (node (ref "C25") (pin "P$2") (pinfunction "2_P$2") (pintype "passive"))
      (node (ref "C27") (pin "P$2") (pinfunction "2_P$2") (pintype "passive"))
      (node (ref "C30") (pin "P$2") (pinfunction "2_P$2") (pintype "passive"))
      (node (ref "C35") (pin "P$2") (pinfunction "2_P$2") (pintype "passive"))
      (node (ref "C36") (pin "P$1") (pinfunction "1_P$1") (pintype "passive"))
      (node (ref "C38") (pin "P$2") (pinfunction "2_P$2") (pintype "passive"))
      (node (ref "C39") (pin "P$1") (pinfunction "1_P$1") (pintype "passive"))
      (node (ref "C4") (pin "P$1") (pinfunction "1_P$1") (pintype "passive"))
      (node (ref "C40") (pin "P$1") (pinfunction "1_P$1") (pintype "passive"))
      (node (ref "C41") (pin "P$1") (pinfunction "1_P$1") (pintype "passive"))
      (node (ref "C43") (pin "P$2") (pinfunction "2_P$2") (pintype "passive"))
      (node (ref "C5") (pin "P$1") (pinfunction "1_P$1") (pintype "passive"))
      (node (ref "C7") (pin "P$1") (pinfunction "1_P$1") (pintype "passive"))
      (node (ref "FB1") (pin "1") (pinfunction "P$1_1") (pintype "bidirectional"))
      (node (ref "J1") (pin "4") (pinfunction "SUPPLY_VOLTAGE_4") (pintype "power_in"))
      (node (ref "J3") (pin "2") (pinfunction "2_2") (pintype "passive"))
      (node (ref "J3") (pin "4") (pinfunction "4_4") (pintype "passive"))
      (node (ref "L1") (pin "2") (pinfunction "P$2_2") (pintype "bidirectional"))
      (node (ref "R13") (pin "P$2") (pinfunction "2_P$2") (pintype "passive"))
      (node (ref "R14") (pin "P$1") (pinfunction "1_P$1") (pintype "passive"))
      (node (ref "R15") (pin "P$1") (pinfunction "1_P$1") (pintype "passive"))
      (node (ref "R2") (pin "P$2") (pinfunction "2_P$2") (pintype "passive"))
      (node (ref "R3") (pin "P$2") (pinfunction "2_P$2") (pintype "passive"))
      (node (ref "R4") (pin "P$2") (pinfunction "2_P$2") (pintype "passive"))
      (node (ref "R5") (pin "P$2") (pinfunction "2_P$2") (pintype "passive"))
      (node (ref "R6") (pin "P$2") (pinfunction "2_P$2") (pintype "passive"))
      (node (ref "R7") (pin "P$2") (pinfunction "2_P$2") (pintype "passive"))
      (node (ref "R8") (pin "P$2") (pinfunction "2_P$2") (pintype "passive"))
      (node (ref "U1") (pin "14") (pinfunction "VDDIO_14") (pintype "power_in"))
      (node (ref "U3") (pin "110") (pinfunction "VCC(IO)5_110") (pintype "bidirectional"))
      (node (ref "U3") (pin "123") (pinfunction "VCC(IO)6_123") (pintype "bidirectional"))
      (node (ref "U3") (pin "138") (pinfunction "VCC(IO)7_138") (pintype "bidirectional"))
      (node (ref "U3") (pin "149") (pinfunction "VCC(IO)8_149") (pintype "bidirectional"))
      (node (ref "U3") (pin "154") (pinfunction "VREFH_154") (pintype "bidirectional"))
      (node (ref "U3") (pin "155") (pinfunction "AVCC0_155") (pintype "bidirectional"))
      (node (ref "U3") (pin "158") (pinfunction "VREFH0_158") (pintype "bidirectional"))
      (node (ref "U3") (pin "171") (pinfunction "VCC(IO)9_171") (pintype "bidirectional"))
      (node (ref "U3") (pin "25") (pinfunction "VCC1_25") (pintype "bidirectional"))
      (node (ref "U3") (pin "26") (pinfunction "AVCC_SUBHS_26") (pintype "bidirectional"))
      (node (ref "U3") (pin "34") (pinfunction "VCC_USBHS_34") (pintype "bidirectional"))
      (node (ref "U3") (pin "48") (pinfunction "VCC_USB_48") (pintype "bidirectional"))
      (node (ref "U3") (pin "61") (pinfunction "VCC(IO)2_61") (pintype "bidirectional"))
      (node (ref "U3") (pin "84") (pinfunction "VCC(IO)3_84") (pintype "bidirectional"))
      (node (ref "U3") (pin "97") (pinfunction "VCC(IO)4_97") (pintype "bidirectional"))
    )
    (net (code "162") (name "VDD5") (class "Default")
      (node (ref "C23") (pin "P$1") (pinfunction "1_P$1") (pintype "passive"))
      (node (ref "C26") (pin "P$1") (pinfunction "1_P$1") (pintype "passive"))
      (node (ref "J2") (pin "P$3") (pinfunction "P$3_P$3") (pintype "bidirectional"))
      (node (ref "R19") (pin "P$2") (pinfunction "2_P$2") (pintype "passive"))
      (node (ref "R20") (pin "P$2") (pinfunction "2_P$2") (pintype "passive"))
      (node (ref "U2") (pin "4") (pinfunction "VIN_4") (pintype "input"))
    )
    (net (code "163") (name "VDDIN") (class "Default")
      (node (ref "J2") (pin "P$2") (pinfunction "P$2_P$2") (pintype "bidirectional"))
      (node (ref "L1") (pin "1") (pinfunction "P$1_1") (pintype "bidirectional"))
    )
    (net (code "164") (name "VDD_1.2") (class "Default")
      (node (ref "C10") (pin "P$1") (pinfunction "1_P$1") (pintype "passive"))
      (node (ref "C11") (pin "P$1") (pinfunction "1_P$1") (pintype "passive"))
      (node (ref "U1") (pin "1") (pinfunction "VDD_1.2_1") (pintype "power_in"))
    )
    (net (code "165") (name "XCIN") (class "Default")
      (node (ref "C32") (pin "P$1") (pinfunction "1_P$1") (pintype "passive"))
      (node (ref "U3") (pin "20") (pinfunction "XCIN_20") (pintype "bidirectional"))
      (node (ref "X3") (pin "P$1") (pinfunction "P$1_P$1") (pintype "bidirectional"))
    )
    (net (code "166") (name "XCOUT") (class "Default")
      (node (ref "C37") (pin "P$1") (pinfunction "1_P$1") (pintype "passive"))
      (node (ref "U3") (pin "21") (pinfunction "XCOUT_21") (pintype "bidirectional"))
      (node (ref "X3") (pin "P$2") (pinfunction "P$2_P$2") (pintype "bidirectional"))
    )
    (net (code "167") (name "XII") (class "Default")
      (node (ref "C1") (pin "P$1") (pinfunction "1_P$1") (pintype "passive"))
      (node (ref "U1") (pin "8") (pinfunction "XI_8") (pintype "input"))
      (node (ref "X1") (pin "1") (pinfunction "1_1") (pintype "bidirectional"))
    )
    (net (code "168") (name "XOO") (class "Default")
      (node (ref "C2") (pin "P$1") (pinfunction "1_P$1") (pintype "passive"))
      (node (ref "U1") (pin "7") (pinfunction "XO_7") (pintype "output"))
      (node (ref "X1") (pin "3") (pinfunction "3_3") (pintype "bidirectional"))
    )
    (net (code "169") (name "XTAL1") (class "Default")
      (node (ref "C17") (pin "P$1") (pinfunction "1_P$1") (pintype "passive"))
      (node (ref "U3") (pin "23") (pinfunction "P2_13/XTAL_23") (pintype "bidirectional"))
      (node (ref "X2") (pin "1") (pinfunction "1_1") (pintype "bidirectional"))
    )
    (net (code "170") (name "XTAL2") (class "Default")
      (node (ref "C18") (pin "P$1") (pinfunction "1_P$1") (pintype "passive"))
      (node (ref "U3") (pin "24") (pinfunction "P2_12/EXTAL_24") (pintype "bidirectional"))
      (node (ref "X2") (pin "3") (pinfunction "3_3") (pintype "bidirectional"))
    )
    (net (code "171") (name "unconnected-(U3-VBAT-Pad18)") (class "Default")
      (node (ref "U3") (pin "18") (pinfunction "VBAT_18") (pintype "bidirectional"))
    )
  )
)
